# Sheet1.net
KiCad netlist of a schematic drawn in Altium Designer
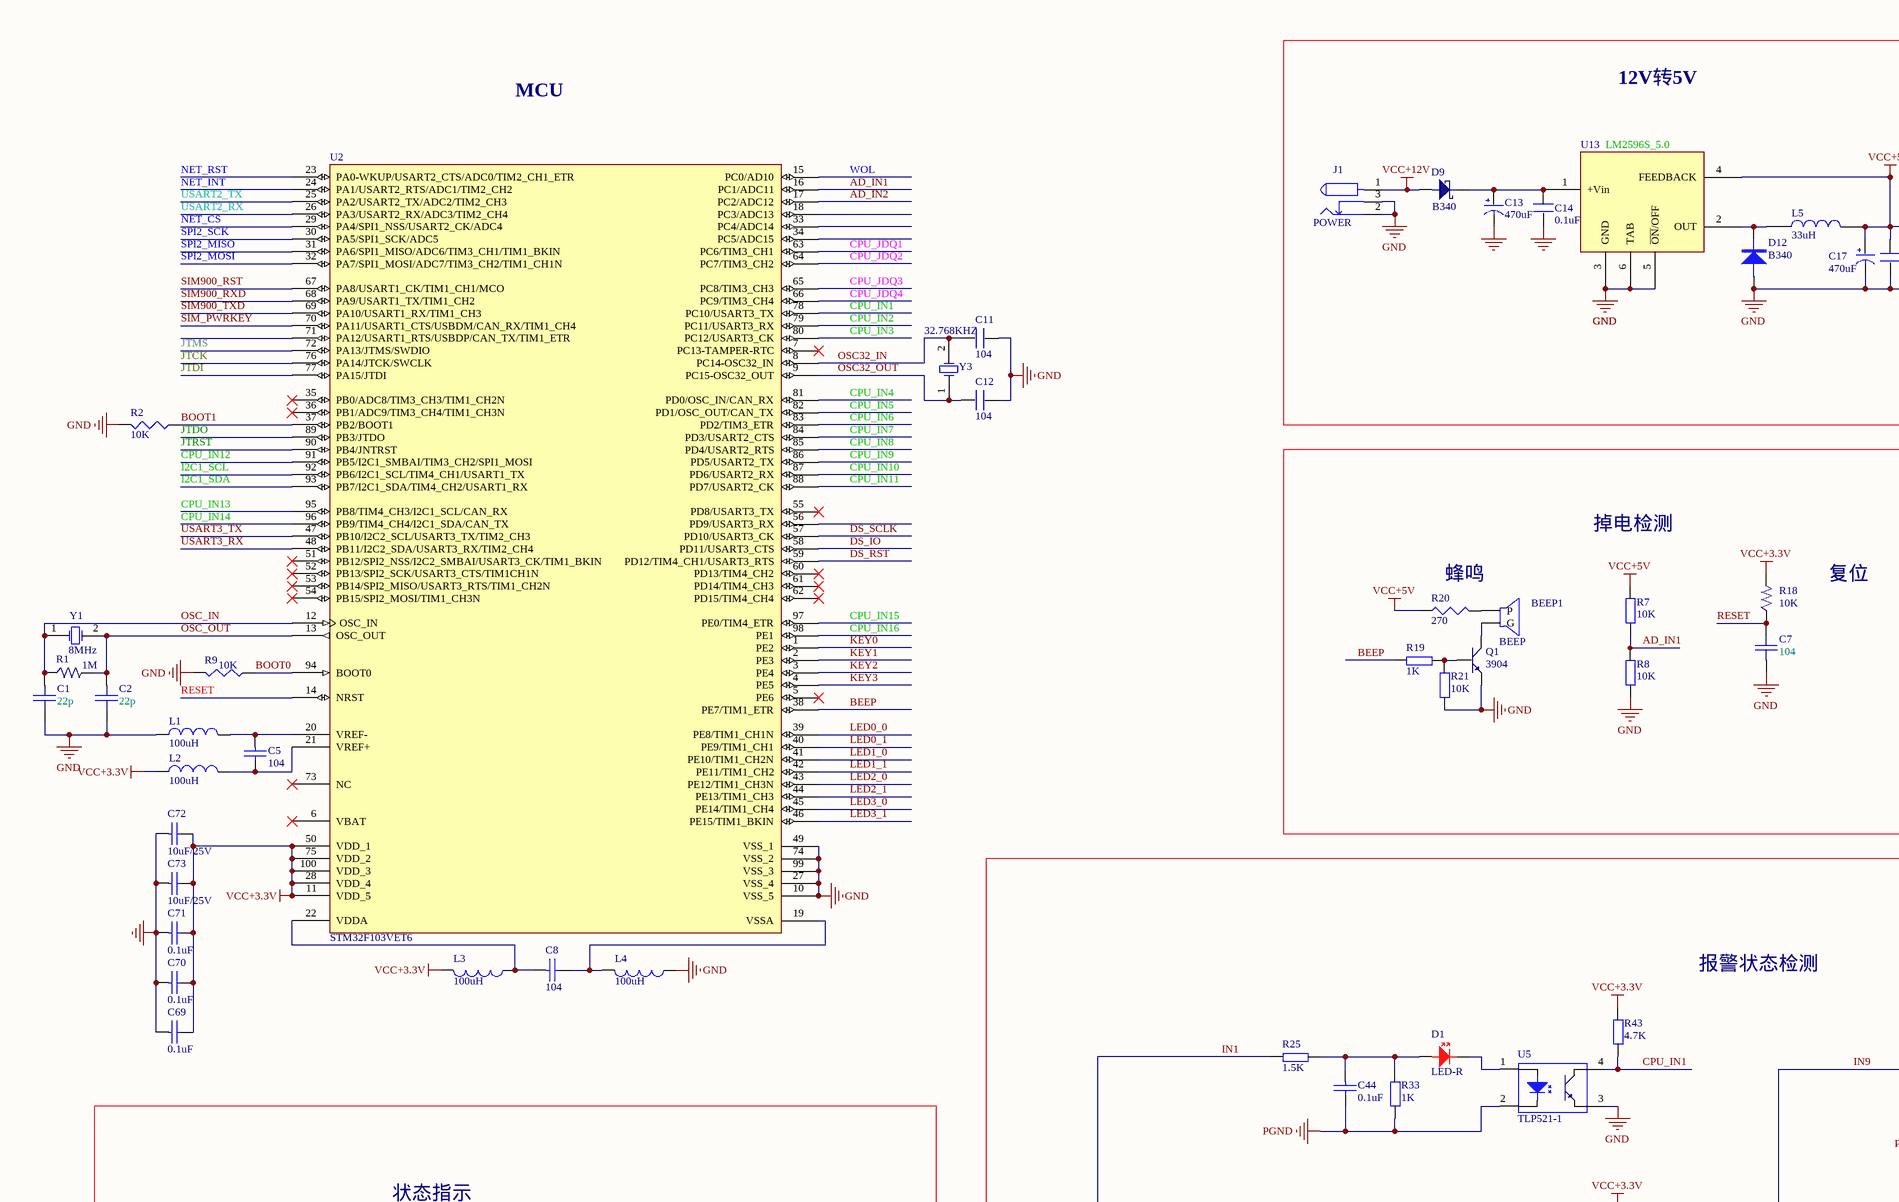
[diagram p0: Sheet1.SchDoc, top left]
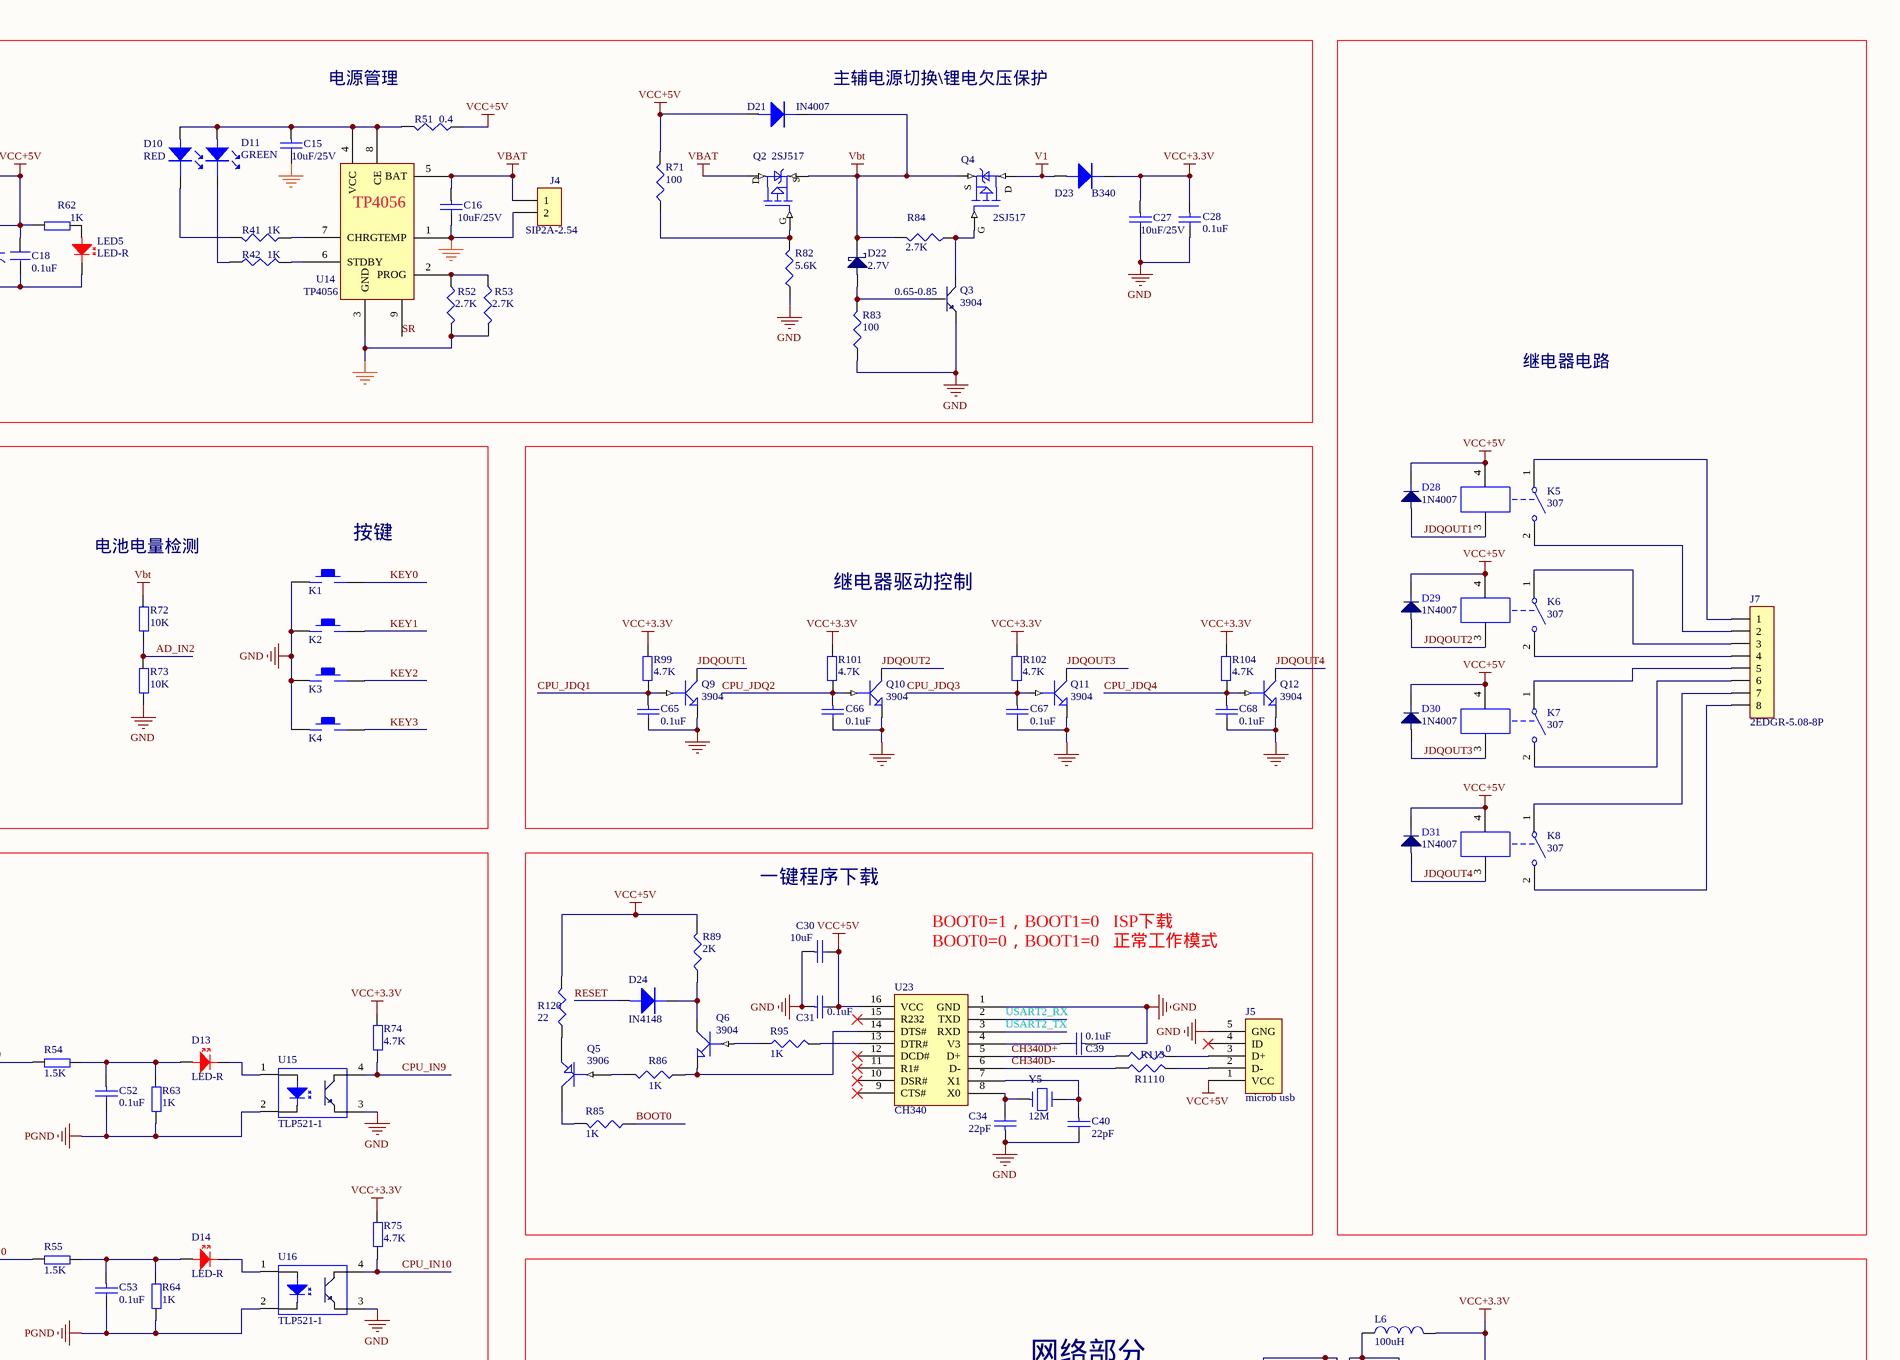
[diagram p1: Sheet1.SchDoc, top right]
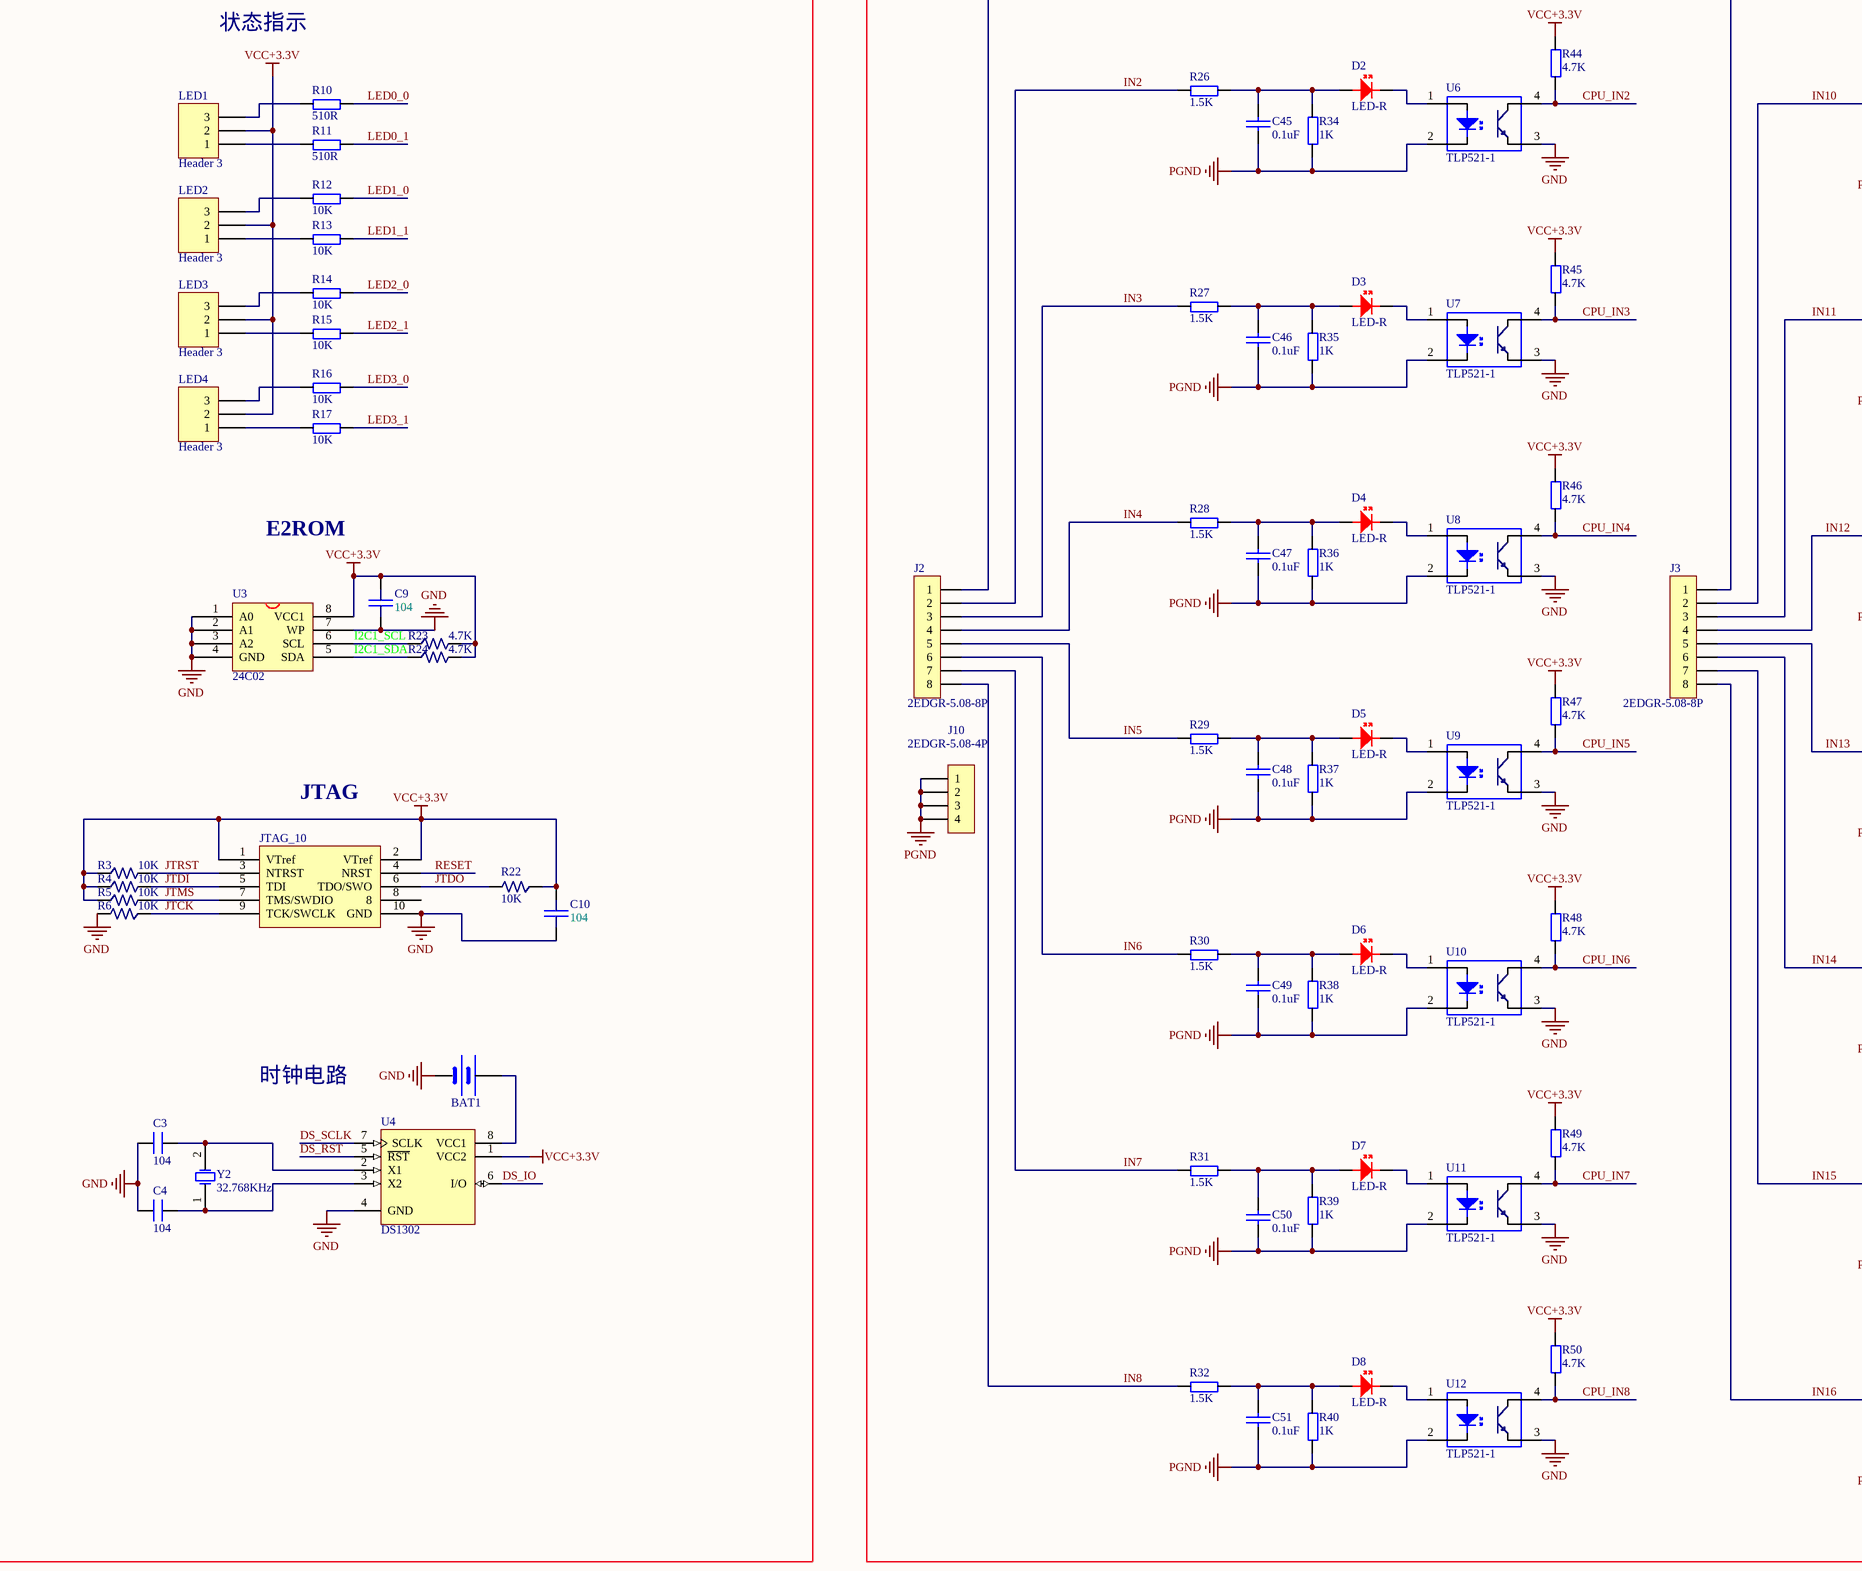
[diagram p2: Sheet1.SchDoc, bottom left]
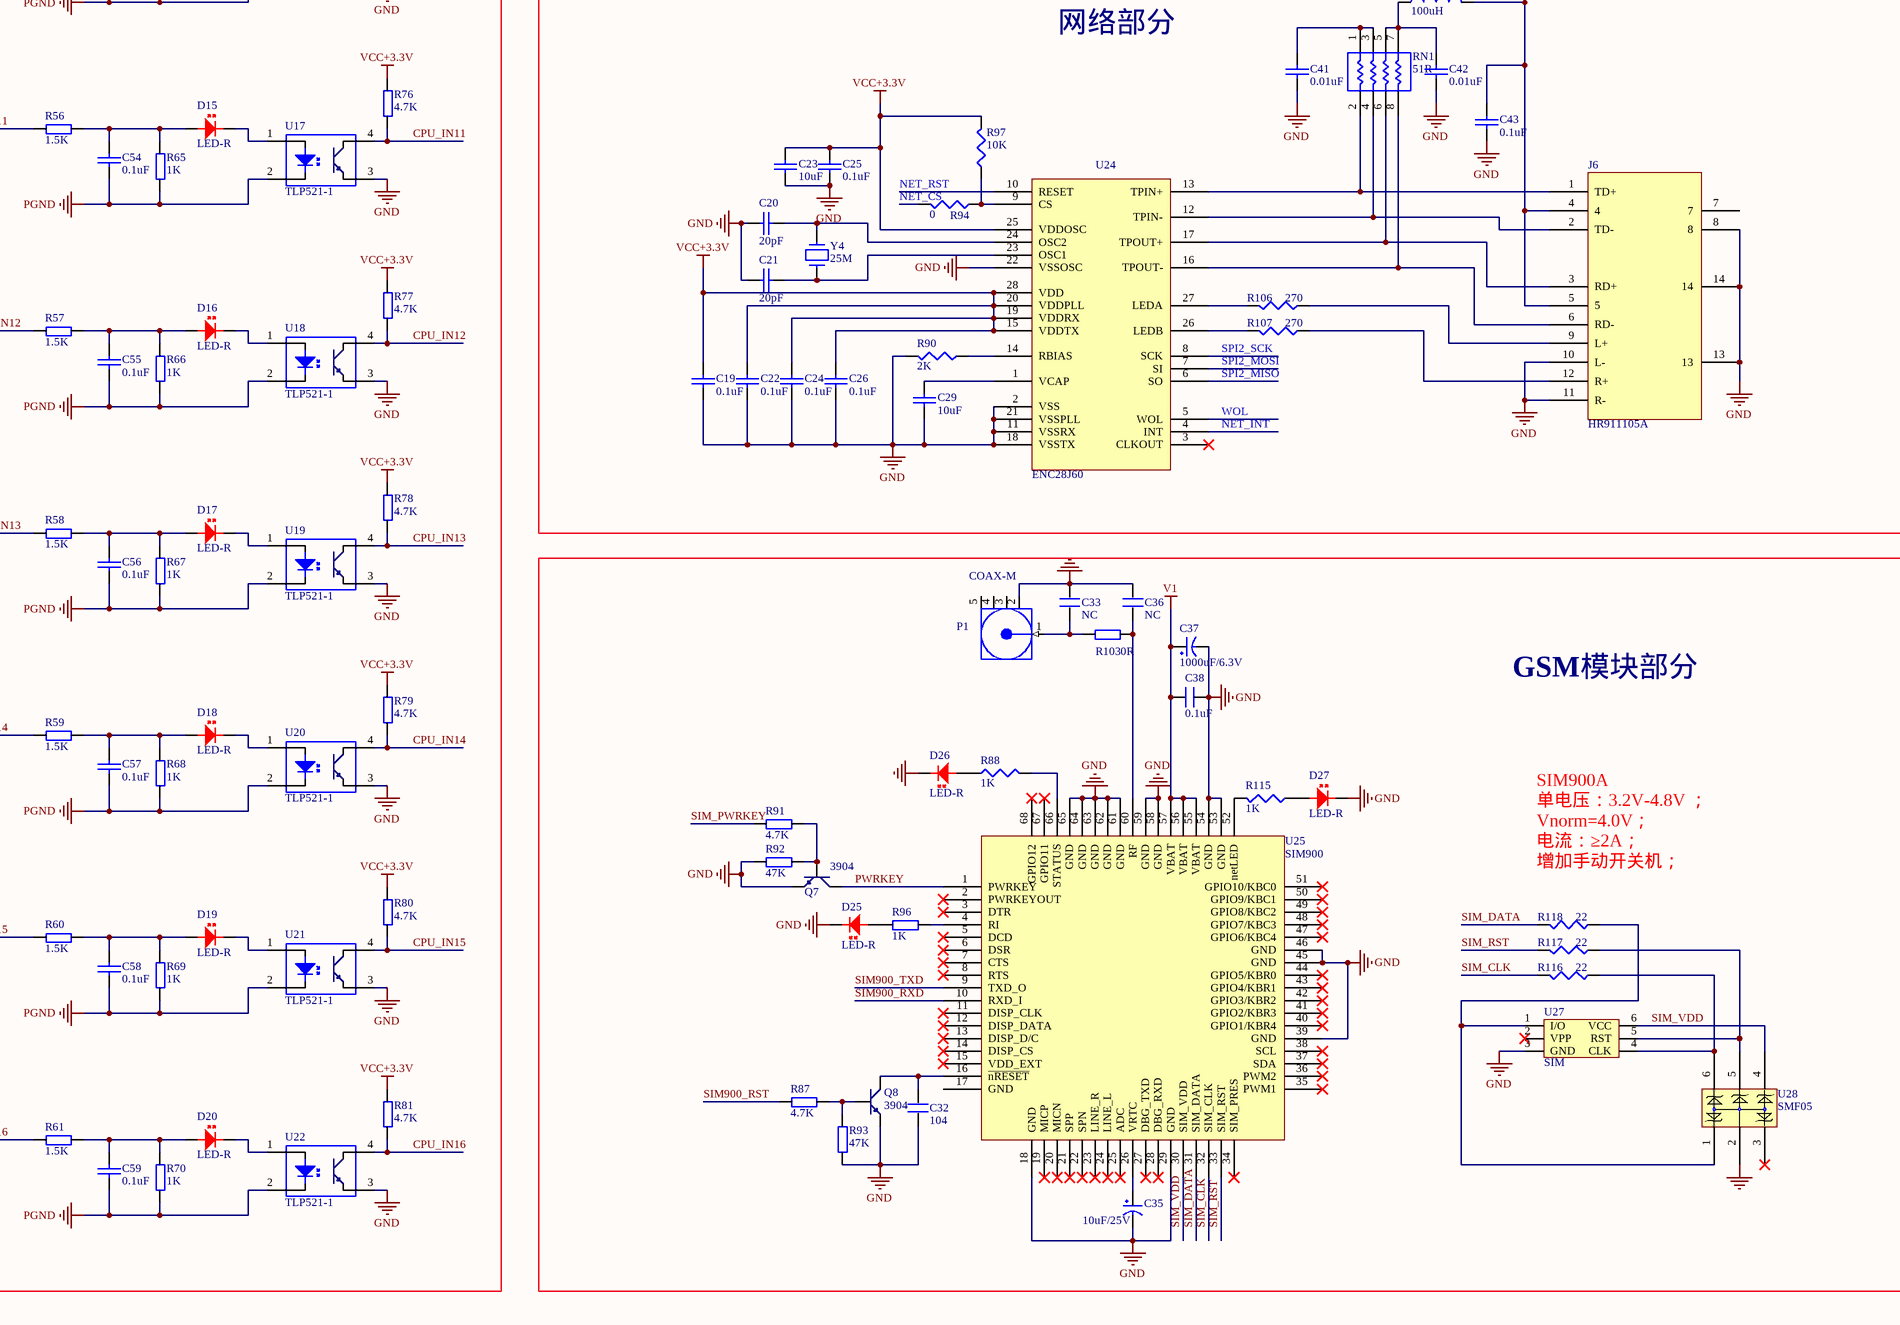
[diagram p3: Sheet1.SchDoc, bottom right]

(export (version "E")
  (design (tool "Eeschema 10.0.6"))
  (components
    (comp (ref "BAT1") (value "BATT") (footprint "CR2032") (libsource (lib "mylib") (part "BAT")))
    (comp (ref "BEEP1") (value "BEEP") (footprint "BEEP-12") (libsource (lib "mylib") (part "BEEP")))
    (comp (ref "C1")
      (value "22p")
      (footprint "0805")
      (description "陶瓷电容")
      (libsource (lib "8CF_V6") (part "CAP"))
    )
    (comp (ref "C2")
      (value "22p")
      (footprint "0805")
      (description "陶瓷电容")
      (libsource (lib "8CF_V6") (part "CAP"))
    )
    (comp (ref "C3") (value "104") (footprint "0805") (libsource (lib "mylib") (part "C")))
    (comp (ref "C4") (value "104") (footprint "0805") (libsource (lib "mylib") (part "C")))
    (comp (ref "C5") (value "104") (footprint "0805") (libsource (lib "INSPUR_SCH") (part "CAP")))
    (comp (ref "C7")
      (value "104")
      (footprint "0805")
      (description "陶瓷电容")
      (libsource (lib "8CF_V6") (part "CAP"))
    )
    (comp (ref "C8") (value "104") (footprint "0805") (libsource (lib "INSPUR_SCH") (part "CAP")))
    (comp (ref "C9")
      (value "104")
      (footprint "0805")
      (description "陶瓷电容")
      (libsource (lib "8CF_V6") (part "CAP"))
    )
    (comp (ref "C10")
      (value "104")
      (footprint "0805")
      (description "陶瓷电容")
      (libsource (lib "8CF_V6") (part "CAP"))
    )
    (comp (ref "C11") (value "104") (footprint "0805") (libsource (lib "mylib") (part "C")))
    (comp (ref "C12") (value "104") (footprint "0805") (libsource (lib "mylib") (part "C")))
    (comp (ref "C13") (value "470uF") (footprint "RB3.5") (libsource (lib "战舰STM32开发板底板") (part "CAP")))
    (comp (ref "C14") (value "0.1uF") (footprint "0805") (libsource (lib "mylib") (part "C")))
    (comp (ref "C15") (value "10uF/25V") (footprint "0805") (libsource (lib "*") (part "CAP")))
    (comp (ref "C16") (value "10uF/25V") (footprint "0805") (libsource (lib "*") (part "CAP")))
    (comp (ref "C17") (value "470uF") (footprint "RB3.5") (libsource (lib "战舰STM32开发板底板") (part "CAP")))
    (comp (ref "C18") (value "0.1uF") (footprint "0805") (libsource (lib "mylib") (part "C")))
    (comp (ref "C19") (value "0.1uF") (footprint "0805") (libsource (lib "INSPUR_SCH") (part "CAP")))
    (comp (ref "C20") (value "20pF") (footprint "0805") (libsource (lib "INSPUR_SCH") (part "CAP")))
    (comp (ref "C21") (value "20pF") (footprint "0805") (libsource (lib "INSPUR_SCH") (part "CAP")))
    (comp (ref "C22") (value "0.1uF") (footprint "0805") (libsource (lib "INSPUR_SCH") (part "CAP")))
    (comp (ref "C23")
      (value "10uF")
      (footprint "0805")
      (description "0.1uF")
      (libsource (lib "INSPUR_SCH") (part "CAP"))
    )
    (comp (ref "C24") (value "0.1uF") (footprint "0805") (libsource (lib "INSPUR_SCH") (part "CAP")))
    (comp (ref "C25") (value "0.1uF") (footprint "0805") (libsource (lib "INSPUR_SCH") (part "CAP")))
    (comp (ref "C26") (value "0.1uF") (footprint "0805") (libsource (lib "INSPUR_SCH") (part "CAP")))
    (comp (ref "C27") (value "10uF/25V") (footprint "0805") (libsource (lib "*") (part "CAP")))
    (comp (ref "C28") (value "0.1uF") (footprint "0805") (libsource (lib "INSPUR_SCH") (part "CAP")))
    (comp (ref "C29") (value "10uF") (footprint "0805") (libsource (lib "INSPUR_SCH") (part "CAP")))
    (comp (ref "C30")
      (value "10uF")
      (footprint "0805")
      (description "0.1uF")
      (libsource (lib "INSPUR_SCH") (part "CAP"))
    )
    (comp (ref "C31") (value "0.1uF") (footprint "0805") (libsource (lib "INSPUR_SCH") (part "CAP")))
    (comp (ref "C32") (value "104") (footprint "0805") (libsource (lib "mylib") (part "C")))
    (comp (ref "C33") (value "NC") (footprint "0805") (libsource (lib "mylib") (part "C")))
    (comp (ref "C34")
      (value "22pF")
      (footprint "0805")
      (description "0.1uF")
      (libsource (lib "INSPUR_SCH") (part "CAP"))
    )
    (comp (ref "C35") (value "10uF/25V") (footprint "1206") (libsource (lib "mylib") (part "CAP")))
    (comp (ref "C36") (value "NC") (footprint "0805") (libsource (lib "mylib") (part "C")))
    (comp (ref "C37") (value "1000uF/6.3V") (footprint "7343") (libsource (lib "") (part "CAP_1")))
    (comp (ref "C38") (value "0.1uF") (footprint "0805") (libsource (lib "mylib") (part "C")))
    (comp (ref "C39") (value "0.1uF") (footprint "0805") (libsource (lib "INSPUR_SCH") (part "CAP")))
    (comp (ref "C40")
      (value "22pF")
      (footprint "0805")
      (description "0.1uF")
      (libsource (lib "INSPUR_SCH") (part "CAP"))
    )
    (comp (ref "C41") (value "0.01uF") (footprint "0805") (libsource (lib "INSPUR_SCH") (part "CAP")))
    (comp (ref "C42") (value "0.01uF") (footprint "0805") (libsource (lib "INSPUR_SCH") (part "CAP")))
    (comp (ref "C43") (value "0.1uF") (footprint "0805") (libsource (lib "INSPUR_SCH") (part "CAP")))
    (comp (ref "C44") (value "0.1uF") (footprint "0805") (libsource (lib "INSPUR_SCH") (part "CAP")))
    (comp (ref "C45") (value "0.1uF") (footprint "0805") (libsource (lib "INSPUR_SCH") (part "CAP")))
    (comp (ref "C46") (value "0.1uF") (footprint "0805") (libsource (lib "INSPUR_SCH") (part "CAP")))
    (comp (ref "C47") (value "0.1uF") (footprint "0805") (libsource (lib "INSPUR_SCH") (part "CAP")))
    (comp (ref "C48") (value "0.1uF") (footprint "0805") (libsource (lib "INSPUR_SCH") (part "CAP")))
    (comp (ref "C49") (value "0.1uF") (footprint "0805") (libsource (lib "INSPUR_SCH") (part "CAP")))
    (comp (ref "C50") (value "0.1uF") (footprint "0805") (libsource (lib "INSPUR_SCH") (part "CAP")))
    (comp (ref "C51") (value "0.1uF") (footprint "0805") (libsource (lib "INSPUR_SCH") (part "CAP")))
    (comp (ref "C52") (value "0.1uF") (footprint "0805") (libsource (lib "INSPUR_SCH") (part "CAP")))
    (comp (ref "C53") (value "0.1uF") (footprint "0805") (libsource (lib "INSPUR_SCH") (part "CAP")))
    (comp (ref "C54") (value "0.1uF") (footprint "0805") (libsource (lib "INSPUR_SCH") (part "CAP")))
    (comp (ref "C55") (value "0.1uF") (footprint "0805") (libsource (lib "INSPUR_SCH") (part "CAP")))
    (comp (ref "C56") (value "0.1uF") (footprint "0805") (libsource (lib "INSPUR_SCH") (part "CAP")))
    (comp (ref "C57") (value "0.1uF") (footprint "0805") (libsource (lib "INSPUR_SCH") (part "CAP")))
    (comp (ref "C58") (value "0.1uF") (footprint "0805") (libsource (lib "INSPUR_SCH") (part "CAP")))
    (comp (ref "C59") (value "0.1uF") (footprint "0805") (libsource (lib "INSPUR_SCH") (part "CAP")))
    (comp (ref "C65") (value "0.1uF") (footprint "0805") (libsource (lib "INSPUR_SCH") (part "CAP")))
    (comp (ref "C66") (value "0.1uF") (footprint "0805") (libsource (lib "INSPUR_SCH") (part "CAP")))
    (comp (ref "C67") (value "0.1uF") (footprint "0805") (libsource (lib "INSPUR_SCH") (part "CAP")))
    (comp (ref "C68") (value "0.1uF") (footprint "0805") (libsource (lib "INSPUR_SCH") (part "CAP")))
    (comp (ref "C69") (value "0.1uF") (footprint "0805") (libsource (lib "INSPUR_SCH") (part "CAP")))
    (comp (ref "C70") (value "0.1uF") (footprint "0805") (libsource (lib "INSPUR_SCH") (part "CAP")))
    (comp (ref "C71") (value "0.1uF") (footprint "0805") (libsource (lib "*") (part "CAP")))
    (comp (ref "C72") (value "10uF/25V") (footprint "0805") (libsource (lib "*") (part "CAP")))
    (comp (ref "C73") (value "10uF/25V") (footprint "0805") (libsource (lib "*") (part "CAP")))
    (comp (ref "D1")
      (value "LED-R")
      (footprint "0805-LED")
      (description "红色LED")
      (libsource (lib "mylib") (part "LED-RED"))
    )
    (comp (ref "D2")
      (value "LED-R")
      (footprint "0805-LED")
      (description "红色LED")
      (libsource (lib "mylib") (part "LED-RED"))
    )
    (comp (ref "D3")
      (value "LED-R")
      (footprint "0805-LED")
      (description "红色LED")
      (libsource (lib "mylib") (part "LED-RED"))
    )
    (comp (ref "D4")
      (value "LED-R")
      (footprint "0805-LED")
      (description "红色LED")
      (libsource (lib "mylib") (part "LED-RED"))
    )
    (comp (ref "D5")
      (value "LED-R")
      (footprint "0805-LED")
      (description "红色LED")
      (libsource (lib "mylib") (part "LED-RED"))
    )
    (comp (ref "D6")
      (value "LED-R")
      (footprint "0805-LED")
      (description "红色LED")
      (libsource (lib "mylib") (part "LED-RED"))
    )
    (comp (ref "D7")
      (value "LED-R")
      (footprint "0805-LED")
      (description "红色LED")
      (libsource (lib "mylib") (part "LED-RED"))
    )
    (comp (ref "D8")
      (value "LED-R")
      (footprint "0805-LED")
      (description "红色LED")
      (libsource (lib "mylib") (part "LED-RED"))
    )
    (comp (ref "D9")
      (value "B340")
      (footprint "SMB")
      (description "肖特基二极管")
      (libsource (lib "mylib") (part "1N5824(SS54)"))
    )
    (comp (ref "D10") (value "RED") (footprint "LED-0805") (libsource (lib "*") (part "LED")))
    (comp (ref "D11") (value "GREEN") (footprint "LED-0805") (libsource (lib "*") (part "LED")))
    (comp (ref "D12") (value "B340") (footprint "SMB") (libsource (lib "INSPUR_SCH") (part "DIODE")))
    (comp (ref "D13")
      (value "LED-R")
      (footprint "0805-LED")
      (description "红色LED")
      (libsource (lib "mylib") (part "LED-RED"))
    )
    (comp (ref "D14")
      (value "LED-R")
      (footprint "0805-LED")
      (description "红色LED")
      (libsource (lib "mylib") (part "LED-RED"))
    )
    (comp (ref "D15")
      (value "LED-R")
      (footprint "0805-LED")
      (description "红色LED")
      (libsource (lib "mylib") (part "LED-RED"))
    )
    (comp (ref "D16")
      (value "LED-R")
      (footprint "0805-LED")
      (description "红色LED")
      (libsource (lib "mylib") (part "LED-RED"))
    )
    (comp (ref "D17")
      (value "LED-R")
      (footprint "0805-LED")
      (description "红色LED")
      (libsource (lib "mylib") (part "LED-RED"))
    )
    (comp (ref "D18")
      (value "LED-R")
      (footprint "0805-LED")
      (description "红色LED")
      (libsource (lib "mylib") (part "LED-RED"))
    )
    (comp (ref "D19")
      (value "LED-R")
      (footprint "0805-LED")
      (description "红色LED")
      (libsource (lib "mylib") (part "LED-RED"))
    )
    (comp (ref "D20")
      (value "LED-R")
      (footprint "0805-LED")
      (description "红色LED")
      (libsource (lib "mylib") (part "LED-RED"))
    )
    (comp (ref "D21")
      (value "IN4007")
      (footprint "SMA(DO-214AC)")
      (libsource (lib "INSPUR_SCH") (part "DIODE"))
    )
    (comp (ref "D22")
      (value "2.7V")
      (footprint "sod-123")
      (description "3V稳压管")
      (libsource (lib "mylib") (part "1N5824(SS54)"))
    )
    (comp (ref "D23") (value "B340") (footprint "SMB") (libsource (lib "INSPUR_SCH") (part "DIODE")))
    (comp (ref "D24") (value "IN4148") (footprint "SOD-23") (libsource (lib "INSPUR_SCH") (part "DIODE")))
    (comp (ref "D25")
      (value "LED-R")
      (footprint "LED-DIP")
      (description "红色LED")
      (libsource (lib "mylib") (part "LED-RED"))
    )
    (comp (ref "D26")
      (value "LED-R")
      (footprint "LED-DIP")
      (description "红色LED")
      (libsource (lib "mylib") (part "LED-RED"))
    )
    (comp (ref "D27")
      (value "LED-R")
      (footprint "LED-DIP")
      (description "红色LED")
      (libsource (lib "mylib") (part "LED-RED"))
    )
    (comp (ref "D28")
      (value "1N4007")
      (footprint "DO-214AC(SMA)")
      (description "1A整流二极管")
      (libsource (lib "mylib") (part "1N4007"))
    )
    (comp (ref "D29")
      (value "1N4007")
      (footprint "DO-214AC(SMA)")
      (description "1A整流二极管")
      (libsource (lib "mylib") (part "1N4007"))
    )
    (comp (ref "D30")
      (value "1N4007")
      (footprint "DO-214AC(SMA)")
      (description "1A整流二极管")
      (libsource (lib "mylib") (part "1N4007"))
    )
    (comp (ref "D31")
      (value "1N4007")
      (footprint "DO-214AC(SMA)")
      (description "1A整流二极管")
      (libsource (lib "mylib") (part "1N4007"))
    )
    (comp (ref "J1") (value "POWER") (footprint "DC10B") (libsource (lib "战舰STM32开发板底板") (part "POW")))
    (comp (ref "J2")
      (value "2EDGR-5.08-8P")
      (footprint "2EDGR-5.08-8P")
      (description "端子")
      (libsource (lib "mylib") (part "2EDGR-5.08-8P"))
    )
    (comp (ref "J3")
      (value "2EDGR-5.08-8P")
      (footprint "2EDGR-5.08-8P")
      (description "端子")
      (libsource (lib "mylib") (part "2EDGR-5.08-8P"))
    )
    (comp (ref "J4") (value "SIP2A-2.54") (footprint "2.54") (libsource (lib "*") (part "SIP2A-2.50（带槽）")))
    (comp (ref "J5")
      (value "microb usb")
      (footprint "USB_micro")
      (libsource (lib "INSPUR_SCH") (part "microb usb"))
    )
    (comp (ref "J6")
      (value "HR911105A")
      (footprint "HR911105A")
      (libsource (lib "INSPUR_SCH") (part "HR911105A"))
    )
    (comp (ref "J7")
      (value "2EDGR-5.08-8P")
      (footprint "2EDGR-5.08-8P")
      (description "端子")
      (libsource (lib "") (part "2EDGR-5.08-8P_1"))
    )
    (comp (ref "J10")
      (value "2EDGR-5.08-4P")
      (footprint "2EDGR-5.08-4P")
      (libsource (lib "INSPUR_SCH") (part "SIP4A-2.50(带槽)"))
    )
    (comp (ref "JTAG_1") (value "JTAG_10") (footprint "JTAG_10") (libsource (lib "mylib") (part "JTAG_10")))
    (comp (ref "K1") (value "KEY_M") (footprint "KEY_M") (libsource (lib "mylib") (part "KEY_M")))
    (comp (ref "K2") (value "KEY_M") (footprint "KEY_M") (libsource (lib "mylib") (part "KEY_M")))
    (comp (ref "K3") (value "KEY_M") (footprint "KEY_M") (libsource (lib "mylib") (part "KEY_M")))
    (comp (ref "K4") (value "KEY_M") (footprint "KEY_M") (libsource (lib "mylib") (part "KEY_M")))
    (comp (ref "K5")
      (value "307")
      (footprint "RELAY-SONGCHUAN")
      (description "继电器")
      (libsource (lib "mylib") (part "JDQ_307"))
    )
    (comp (ref "K6")
      (value "307")
      (footprint "RELAY-SONGCHUAN")
      (description "继电器")
      (libsource (lib "mylib") (part "JDQ_307"))
    )
    (comp (ref "K7")
      (value "307")
      (footprint "RELAY-SONGCHUAN")
      (description "继电器")
      (libsource (lib "mylib") (part "JDQ_307"))
    )
    (comp (ref "K8")
      (value "307")
      (footprint "RELAY-SONGCHUAN")
      (description "继电器")
      (libsource (lib "mylib") (part "JDQ_307"))
    )
    (comp (ref "L1") (value "100uH") (footprint "0805") (libsource (lib "INSPUR_SCH") (part "INDUCTOR")))
    (comp (ref "L2") (value "100uH") (footprint "0805") (libsource (lib "INSPUR_SCH") (part "INDUCTOR")))
    (comp (ref "L3") (value "100uH") (footprint "0805") (libsource (lib "INSPUR_SCH") (part "INDUCTOR")))
    (comp (ref "L4") (value "100uH") (footprint "0805") (libsource (lib "INSPUR_SCH") (part "INDUCTOR")))
    (comp (ref "L5") (value "33uH") (footprint "INDUCTOR-1212") (libsource (lib "mylib") (part "INDUCTOR")))
    (comp (ref "L6") (value "100uH") (footprint "0805") (libsource (lib "INSPUR_SCH") (part "INDUCTOR")))
    (comp (ref "LED1")
      (value "Header 3")
      (footprint "HDR1X3")
      (description "Header, 3-Pin")
      (fields (field (name "PUBLISHER") "Altium Limited"))
      (libsource (lib "Miscellaneous Connectors") (part "Header 3"))
    )
    (comp (ref "LED2")
      (value "Header 3")
      (footprint "HDR1X3")
      (description "Header, 3-Pin")
      (fields (field (name "PUBLISHER") "Altium Limited"))
      (libsource (lib "Miscellaneous Connectors") (part "Header 3"))
    )
    (comp (ref "LED3")
      (value "Header 3")
      (footprint "HDR1X3")
      (description "Header, 3-Pin")
      (fields (field (name "PUBLISHER") "Altium Limited"))
      (libsource (lib "Miscellaneous Connectors") (part "Header 3"))
    )
    (comp (ref "LED4")
      (value "Header 3")
      (footprint "HDR1X3")
      (description "Header, 3-Pin")
      (fields (field (name "PUBLISHER") "Altium Limited"))
      (libsource (lib "Miscellaneous Connectors") (part "Header 3"))
    )
    (comp (ref "LED5")
      (value "LED-R")
      (footprint "LED-0805")
      (description "红色LED")
      (libsource (lib "mylib") (part "LED-RED"))
    )
    (comp (ref "P1")
      (value "COAX-M")
      (footprint "ST-TH1")
      (description "SMA-J-P-H-ST-TH1")
      (fields (field (name "PUBLISHER") "Altium Limited"))
      (libsource (lib "Miscellaneous Connectors") (part "COAX-M"))
    )
    (comp (ref "Q1")
      (value "3904")
      (footprint "SOT-23")
      (description "8050/BCW846/BCW847")
      (libsource (lib "mylib") (part "NPN"))
    )
    (comp (ref "Q2") (value "2SJ517") (footprint "SOT-89") (libsource (lib "*") (part "MOSFET P_1")))
    (comp (ref "Q3")
      (value "3904")
      (footprint "SOT-23")
      (description "8050/BCW846/BCW847")
      (libsource (lib "mylib") (part "NPN"))
    )
    (comp (ref "Q4") (value "2SJ517") (footprint "SOT-89") (libsource (lib "*") (part "MOSFET P_1")))
    (comp (ref "Q5") (value "3906") (footprint "SOT-23") (libsource (lib "INSPUR_SCH") (part "PNP1")))
    (comp (ref "Q6") (value "3904") (footprint "SOT-23") (libsource (lib "INSPUR_SCH") (part "NPN1")))
    (comp (ref "Q7")
      (value "3904")
      (footprint "SOT-23R")
      (description "8050/BCW846/BCW847")
      (libsource (lib "mylib") (part "NPN"))
    )
    (comp (ref "Q8")
      (value "3904")
      (footprint "SOT-23R")
      (description "8050/BCW846/BCW847")
      (libsource (lib "mylib") (part "NPN"))
    )
    (comp (ref "Q9") (value "3904") (footprint "SOT-23") (libsource (lib "INSPUR_SCH") (part "NPN1")))
    (comp (ref "Q10") (value "3904") (footprint "SOT-23") (libsource (lib "INSPUR_SCH") (part "NPN1")))
    (comp (ref "Q11") (value "3904") (footprint "SOT-23") (libsource (lib "INSPUR_SCH") (part "NPN1")))
    (comp (ref "Q12") (value "3904") (footprint "SOT-23") (libsource (lib "INSPUR_SCH") (part "NPN1")))
    (comp (ref "R1")
      (value "1M")
      (footprint "0805")
      (description "高精度电阻")
      (libsource (lib "8CF_V6") (part "RES-1%"))
    )
    (comp (ref "R2") (value "10K") (footprint "0805") (libsource (lib "INSPUR_SCH") (part "RES1")))
    (comp (ref "R3")
      (value "10K")
      (footprint "0805")
      (description "高精度电阻")
      (libsource (lib "8CF_V6") (part "RES-1%"))
    )
    (comp (ref "R4")
      (value "10K")
      (footprint "0805")
      (description "高精度电阻")
      (libsource (lib "8CF_V6") (part "RES-1%"))
    )
    (comp (ref "R5")
      (value "10K")
      (footprint "0805")
      (description "高精度电阻")
      (libsource (lib "8CF_V6") (part "RES-1%"))
    )
    (comp (ref "R6")
      (value "10K")
      (footprint "0805")
      (description "高精度电阻")
      (libsource (lib "8CF_V6") (part "RES-1%"))
    )
    (comp (ref "R7") (value "10K") (footprint "0805") (libsource (lib "mylib") (part "Res")))
    (comp (ref "R8") (value "10K") (footprint "0805") (libsource (lib "mylib") (part "Res")))
    (comp (ref "R9") (value "10K") (footprint "0805") (libsource (lib "INSPUR_SCH") (part "RES1")))
    (comp (ref "R10") (value "510R") (footprint "0805") (libsource (lib "mylib") (part "Res")))
    (comp (ref "R11") (value "510R") (footprint "0805") (libsource (lib "mylib") (part "Res")))
    (comp (ref "R12") (value "10K") (footprint "0805") (libsource (lib "mylib") (part "Res")))
    (comp (ref "R13") (value "10K") (footprint "0805") (libsource (lib "mylib") (part "Res")))
    (comp (ref "R14") (value "10K") (footprint "0805") (libsource (lib "mylib") (part "Res")))
    (comp (ref "R15") (value "10K") (footprint "0805") (libsource (lib "mylib") (part "Res")))
    (comp (ref "R16") (value "10K") (footprint "0805") (libsource (lib "mylib") (part "Res")))
    (comp (ref "R17") (value "10K") (footprint "0805") (libsource (lib "mylib") (part "Res")))
    (comp (ref "R18")
      (value "10K")
      (footprint "0805")
      (description "高精度电阻")
      (libsource (lib "8CF_V6") (part "RES-1%"))
    )
    (comp (ref "R19") (value "1K") (footprint "0805") (libsource (lib "mylib") (part "R")))
    (comp (ref "R20") (value "270") (footprint "0805") (libsource (lib "INSPUR_SCH") (part "RES1")))
    (comp (ref "R21") (value "10K") (footprint "0805") (libsource (lib "mylib") (part "R")))
    (comp (ref "R22")
      (value "10K")
      (footprint "0805")
      (description "高精度电阻")
      (libsource (lib "8CF_V6") (part "RES-1%"))
    )
    (comp (ref "R23")
      (value "4.7K")
      (footprint "0805")
      (description "高精度电阻")
      (libsource (lib "8CF_V6") (part "RES-1%"))
    )
    (comp (ref "R24")
      (value "4.7K")
      (footprint "0805")
      (description "高精度电阻")
      (libsource (lib "8CF_V6") (part "RES-1%"))
    )
    (comp (ref "R25") (value "1.5K") (footprint "0805") (libsource (lib "mylib") (part "Res")))
    (comp (ref "R26") (value "1.5K") (footprint "0805") (libsource (lib "mylib") (part "Res")))
    (comp (ref "R27") (value "1.5K") (footprint "0805") (libsource (lib "mylib") (part "Res")))
    (comp (ref "R28") (value "1.5K") (footprint "0805") (libsource (lib "mylib") (part "Res")))
    (comp (ref "R29") (value "1.5K") (footprint "0805") (libsource (lib "mylib") (part "Res")))
    (comp (ref "R30") (value "1.5K") (footprint "0805") (libsource (lib "mylib") (part "Res")))
    (comp (ref "R31") (value "1.5K") (footprint "0805") (libsource (lib "mylib") (part "Res")))
    (comp (ref "R32") (value "1.5K") (footprint "0805") (libsource (lib "mylib") (part "Res")))
    (comp (ref "R33") (value "1K") (footprint "0805") (libsource (lib "mylib") (part "Res")))
    (comp (ref "R34") (value "1K") (footprint "0805") (libsource (lib "mylib") (part "Res")))
    (comp (ref "R35") (value "1K") (footprint "0805") (libsource (lib "mylib") (part "Res")))
    (comp (ref "R36") (value "1K") (footprint "0805") (libsource (lib "mylib") (part "Res")))
    (comp (ref "R37") (value "1K") (footprint "0805") (libsource (lib "mylib") (part "Res")))
    (comp (ref "R38") (value "1K") (footprint "0805") (libsource (lib "mylib") (part "Res")))
    (comp (ref "R39") (value "1K") (footprint "0805") (libsource (lib "mylib") (part "Res")))
    (comp (ref "R40") (value "1K") (footprint "0805") (libsource (lib "mylib") (part "Res")))
    (comp (ref "R41") (value "1K") (footprint "0805") (libsource (lib "*") (part "RES1")))
    (comp (ref "R42") (value "1K") (footprint "0805") (libsource (lib "*") (part "RES1")))
    (comp (ref "R43") (value "4.7K") (footprint "0805") (libsource (lib "mylib") (part "Res")))
    (comp (ref "R44") (value "4.7K") (footprint "0805") (libsource (lib "mylib") (part "Res")))
    (comp (ref "R45") (value "4.7K") (footprint "0805") (libsource (lib "mylib") (part "Res")))
    (comp (ref "R46") (value "4.7K") (footprint "0805") (libsource (lib "mylib") (part "Res")))
    (comp (ref "R47") (value "4.7K") (footprint "0805") (libsource (lib "mylib") (part "Res")))
    (comp (ref "R48") (value "4.7K") (footprint "0805") (libsource (lib "mylib") (part "Res")))
    (comp (ref "R49") (value "4.7K") (footprint "0805") (libsource (lib "mylib") (part "Res")))
    (comp (ref "R50") (value "4.7K") (footprint "0805") (libsource (lib "mylib") (part "Res")))
    (comp (ref "R51") (value "0.4") (footprint "1206") (libsource (lib "*") (part "RES1")))
    (comp (ref "R52") (value "2.7K") (footprint "0805") (libsource (lib "*") (part "RES1")))
    (comp (ref "R53") (value "2.7K") (footprint "0805") (libsource (lib "*") (part "RES1")))
    (comp (ref "R54") (value "1.5K") (footprint "0805") (libsource (lib "mylib") (part "Res")))
    (comp (ref "R55") (value "1.5K") (footprint "0805") (libsource (lib "mylib") (part "Res")))
    (comp (ref "R56") (value "1.5K") (footprint "0805") (libsource (lib "mylib") (part "Res")))
    (comp (ref "R57") (value "1.5K") (footprint "0805") (libsource (lib "mylib") (part "Res")))
    (comp (ref "R58") (value "1.5K") (footprint "0805") (libsource (lib "mylib") (part "Res")))
    (comp (ref "R59") (value "1.5K") (footprint "0805") (libsource (lib "mylib") (part "Res")))
    (comp (ref "R60") (value "1.5K") (footprint "0805") (libsource (lib "mylib") (part "Res")))
    (comp (ref "R61") (value "1.5K") (footprint "0805") (libsource (lib "mylib") (part "Res")))
    (comp (ref "R62") (value "1K") (footprint "0805") (libsource (lib "mylib") (part "Res")))
    (comp (ref "R63") (value "1K") (footprint "0805") (libsource (lib "mylib") (part "Res")))
    (comp (ref "R64") (value "1K") (footprint "0805") (libsource (lib "mylib") (part "Res")))
    (comp (ref "R65") (value "1K") (footprint "0805") (libsource (lib "mylib") (part "Res")))
    (comp (ref "R66") (value "1K") (footprint "0805") (libsource (lib "mylib") (part "Res")))
    (comp (ref "R67") (value "1K") (footprint "0805") (libsource (lib "mylib") (part "Res")))
    (comp (ref "R68") (value "1K") (footprint "0805") (libsource (lib "mylib") (part "Res")))
    (comp (ref "R69") (value "1K") (footprint "0805") (libsource (lib "mylib") (part "Res")))
    (comp (ref "R70") (value "1K") (footprint "0805") (libsource (lib "mylib") (part "Res")))
    (comp (ref "R71")
      (value "100")
      (footprint "0805")
      (description "Resistor")
      (libsource (lib "*") (part "RESISTOR"))
    )
    (comp (ref "R72") (value "10K") (footprint "0805") (libsource (lib "mylib") (part "Res")))
    (comp (ref "R73") (value "10K") (footprint "0805") (libsource (lib "mylib") (part "Res")))
    (comp (ref "R74") (value "4.7K") (footprint "0805") (libsource (lib "mylib") (part "Res")))
    (comp (ref "R75") (value "4.7K") (footprint "0805") (libsource (lib "mylib") (part "Res")))
    (comp (ref "R76") (value "4.7K") (footprint "0805") (libsource (lib "mylib") (part "Res")))
    (comp (ref "R77") (value "4.7K") (footprint "0805") (libsource (lib "mylib") (part "Res")))
    (comp (ref "R78") (value "4.7K") (footprint "0805") (libsource (lib "mylib") (part "Res")))
    (comp (ref "R79") (value "4.7K") (footprint "0805") (libsource (lib "mylib") (part "Res")))
    (comp (ref "R80") (value "4.7K") (footprint "0805") (libsource (lib "mylib") (part "Res")))
    (comp (ref "R81") (value "4.7K") (footprint "0805") (libsource (lib "mylib") (part "Res")))
    (comp (ref "R82")
      (value "5.6K")
      (footprint "0805")
      (description "Resistor")
      (libsource (lib "*") (part "RESISTOR"))
    )
    (comp (ref "R83")
      (value "100")
      (footprint "0805")
      (description "Resistor")
      (libsource (lib "*") (part "RESISTOR"))
    )
    (comp (ref "R84")
      (value "2.7K")
      (footprint "0805")
      (description "Resistor")
      (libsource (lib "*") (part "RESISTOR"))
    )
    (comp (ref "R85") (value "1K") (footprint "0805") (libsource (lib "INSPUR_SCH") (part "RES1")))
    (comp (ref "R86") (value "1K") (footprint "0805") (libsource (lib "INSPUR_SCH") (part "RES1")))
    (comp (ref "R87") (value "4.7K") (footprint "0805") (libsource (lib "mylib") (part "Res")))
    (comp (ref "R88") (value "1K") (footprint "0805") (libsource (lib "INSPUR_SCH") (part "RES1")))
    (comp (ref "R89") (value "2K") (footprint "0805") (libsource (lib "INSPUR_SCH") (part "RES1")))
    (comp (ref "R90") (value "2K") (footprint "0805") (libsource (lib "INSPUR_SCH") (part "RES1")))
    (comp (ref "R91") (value "4.7K") (footprint "0805") (libsource (lib "mylib") (part "Res")))
    (comp (ref "R92") (value "47K") (footprint "0805") (libsource (lib "mylib") (part "Res")))
    (comp (ref "R93") (value "47K") (footprint "0805") (libsource (lib "mylib") (part "Res")))
    (comp (ref "R94") (value "0") (footprint "0805") (libsource (lib "INSPUR_SCH") (part "RES1")))
    (comp (ref "R95") (value "1K") (footprint "0805") (libsource (lib "INSPUR_SCH") (part "RES1")))
    (comp (ref "R96") (value "1K") (footprint "0805") (libsource (lib "mylib") (part "Res")))
    (comp (ref "R97") (value "10K") (footprint "0805") (libsource (lib "INSPUR_SCH") (part "RES1")))
    (comp (ref "R99") (value "4.7K") (footprint "0805") (libsource (lib "mylib") (part "Res")))
    (comp (ref "R101") (value "4.7K") (footprint "0805") (libsource (lib "mylib") (part "Res")))
    (comp (ref "R102") (value "4.7K") (footprint "0805") (libsource (lib "mylib") (part "Res")))
    (comp (ref "R103") (value "0R") (footprint "0603") (libsource (lib "mylib") (part "Res")))
    (comp (ref "R104") (value "4.7K") (footprint "0805") (libsource (lib "mylib") (part "Res")))
    (comp (ref "R106") (value "270") (footprint "0805") (libsource (lib "INSPUR_SCH") (part "RES1")))
    (comp (ref "R107") (value "270") (footprint "0805") (libsource (lib "INSPUR_SCH") (part "RES1")))
    (comp (ref "R111") (value "0") (footprint "0805") (libsource (lib "INSPUR_SCH") (part "RES1")))
    (comp (ref "R113") (value "0") (footprint "0805") (libsource (lib "INSPUR_SCH") (part "RES1")))
    (comp (ref "R115") (value "1K") (footprint "0805") (libsource (lib "INSPUR_SCH") (part "RES1")))
    (comp (ref "R116") (value "22") (footprint "0805") (libsource (lib "INSPUR_SCH") (part "RES1")))
    (comp (ref "R117") (value "22") (footprint "0805") (libsource (lib "INSPUR_SCH") (part "RES1")))
    (comp (ref "R118") (value "22") (footprint "0805") (libsource (lib "INSPUR_SCH") (part "RES1")))
    (comp (ref "R120") (value "22") (footprint "0805") (libsource (lib "INSPUR_SCH") (part "RES1")))
    (comp (ref "RN1") (value "51R") (footprint "0603-4") (libsource (lib "INSPUR_SCH") (part "RESPACK")))
    (comp (ref "U2")
      (value "STM32F103VET6")
      (footprint "LQFP100_N")
      (description "STM32 ARM-based 32-bit MCU with 64 Kbytes Flash, 100-pin LQFP, Industrial Temperature")
      (fields (field (name "PUBLISHER") "Altium Limited"))
      (libsource (lib "mylib") (part "STM32F103VET6"))
    )
    (comp (ref "U3") (value "24C02") (footprint "SOP-8") (libsource (lib "战舰STM32开发板底板") (part "24C256")))
    (comp (ref "U4")
      (value "DS1302")
      (footprint "SOP-8")
      (description "实时时钟")
      (libsource (lib "mylib") (part "DS1302"))
    )
    (comp (ref "U5")
      (value "TLP521-1")
      (footprint "DIP4")
      (description "光耦")
      (libsource (lib "mylib") (part "TLP521"))
    )
    (comp (ref "U6")
      (value "TLP521-1")
      (footprint "DIP4")
      (description "光耦")
      (libsource (lib "mylib") (part "TLP521"))
    )
    (comp (ref "U7")
      (value "TLP521-1")
      (footprint "DIP4")
      (description "光耦")
      (libsource (lib "mylib") (part "TLP521"))
    )
    (comp (ref "U8")
      (value "TLP521-1")
      (footprint "DIP4")
      (description "光耦")
      (libsource (lib "mylib") (part "TLP521"))
    )
    (comp (ref "U9")
      (value "TLP521-1")
      (footprint "DIP4")
      (description "光耦")
      (libsource (lib "mylib") (part "TLP521"))
    )
    (comp (ref "U10")
      (value "TLP521-1")
      (footprint "DIP4")
      (description "光耦")
      (libsource (lib "mylib") (part "TLP521"))
    )
    (comp (ref "U11")
      (value "TLP521-1")
      (footprint "DIP4")
      (description "光耦")
      (libsource (lib "mylib") (part "TLP521"))
    )
    (comp (ref "U12")
      (value "TLP521-1")
      (footprint "DIP4")
      (description "光耦")
      (libsource (lib "mylib") (part "TLP521"))
    )
    (comp (ref "U13")
      (value "LM2596S_5.0")
      (footprint "TO-263-5")
      (description "3A开关电源芯片")
      (libsource (lib "Zhuangzaiji") (part "LM2596S_5.0"))
    )
    (comp (ref "U14") (value "TP4056") (footprint "SO8E") (libsource (lib "*") (part "TP4056")))
    (comp (ref "U15")
      (value "TLP521-1")
      (footprint "DIP4")
      (description "光耦")
      (libsource (lib "mylib") (part "TLP521"))
    )
    (comp (ref "U16")
      (value "TLP521-1")
      (footprint "DIP4")
      (description "光耦")
      (libsource (lib "mylib") (part "TLP521"))
    )
    (comp (ref "U17")
      (value "TLP521-1")
      (footprint "DIP4")
      (description "光耦")
      (libsource (lib "mylib") (part "TLP521"))
    )
    (comp (ref "U18")
      (value "TLP521-1")
      (footprint "DIP4")
      (description "光耦")
      (libsource (lib "mylib") (part "TLP521"))
    )
    (comp (ref "U19")
      (value "TLP521-1")
      (footprint "DIP4")
      (description "光耦")
      (libsource (lib "mylib") (part "TLP521"))
    )
    (comp (ref "U20")
      (value "TLP521-1")
      (footprint "DIP4")
      (description "光耦")
      (libsource (lib "mylib") (part "TLP521"))
    )
    (comp (ref "U21")
      (value "TLP521-1")
      (footprint "DIP4")
      (description "光耦")
      (libsource (lib "mylib") (part "TLP521"))
    )
    (comp (ref "U22")
      (value "TLP521-1")
      (footprint "DIP4")
      (description "光耦")
      (libsource (lib "mylib") (part "TLP521"))
    )
    (comp (ref "U23") (value "CH340") (footprint "SOP16") (libsource (lib "INSPUR_SCH") (part "CH340")))
    (comp (ref "U24")
      (value "ENC28J60")
      (footprint "ssop28")
      (libsource (lib "INSPUR_SCH") (part "ENC28J60"))
    )
    (comp (ref "U25") (value "SIM900") (footprint "SIM-900") (libsource (lib "ATK-SIM900A") (part "SIM900")))
    (comp (ref "U27")
      (value "SIM")
      (footprint "sim-6p")
      (description "手机SIM卡")
      (libsource (lib "ATK-SIM900A") (part "SIM"))
    )
    (comp (ref "U28") (value "SMF05") (footprint "SC70-6L") (libsource (lib "INSPUR_SCH") (part "SMF05")))
    (comp (ref "Y1")
      (value "8MHz")
      (footprint "XTAL_US")
      (description "Crystal Oscillator")
      (fields (field (name "PUBLISHER") "Altium Limited"))
      (libsource (lib "mylib") (part "XTAL"))
    )
    (comp (ref "Y2")
      (value "32.768KHz")
      (footprint "cs-308")
      (description "Crystal Oscillator")
      (fields (field (name "PUBLISHER") "Altium Limited"))
      (libsource (lib "mylib") (part "XTAL"))
    )
    (comp (ref "Y3")
      (value "32.768KHZ")
      (footprint "CS-308")
      (description "Crystal Oscillator")
      (fields (field (name "PUBLISHER") "Altium Limited"))
      (libsource (lib "mylib") (part "XTAL"))
    )
    (comp (ref "Y4") (value "25M") (footprint "XTAL_US") (libsource (lib "INSPUR_SCH") (part "CRYSTAL")))
    (comp (ref "Y5") (value "12M") (footprint "XTAL_US") (libsource (lib "INSPUR_SCH") (part "CRYSTAL")))
  )
  (nets
    (net (code "1") (name "/AD_IN1") (class "Default")
      (node (ref "R7") (pin "1") (pintype "passive"))
      (node (ref "R8") (pin "2") (pintype "passive"))
      (node (ref "U2") (pin "16") (pinfunction "PC1/ADC11_16") (pintype "bidirectional"))
    )
    (net (code "2") (name "/AD_IN2") (class "Default")
      (node (ref "R72") (pin "1") (pintype "passive"))
      (node (ref "R73") (pin "2") (pintype "passive"))
      (node (ref "U2") (pin "17") (pinfunction "PC2/ADC12_17") (pintype "bidirectional"))
    )
    (net (code "3") (name "/BEEP") (class "Default")
      (node (ref "R19") (pin "1") (pintype "passive"))
      (node (ref "U2") (pin "38") (pinfunction "PE7/TIM1_ETR_38") (pintype "bidirectional"))
    )
    (net (code "4") (name "/BOOT0") (class "Default")
      (node (ref "R85") (pin "1") (pinfunction "1_1") (pintype "passive"))
      (node (ref "R9") (pin "1") (pinfunction "1_1") (pintype "passive"))
      (node (ref "U2") (pin "94") (pinfunction "BOOT0_94") (pintype "input"))
    )
    (net (code "5") (name "/BOOT1") (class "Default")
      (node (ref "R2") (pin "1") (pinfunction "1_1") (pintype "passive"))
      (node (ref "U2") (pin "37") (pinfunction "PB2/BOOT1_37") (pintype "bidirectional"))
    )
    (net (code "6") (name "/CH340D+") (class "Default")
      (node (ref "R113") (pin "1") (pinfunction "1_1") (pintype "passive"))
      (node (ref "U23") (pin "5") (pinfunction "D+_5") (pintype "passive"))
    )
    (net (code "7") (name "/CH340D-") (class "Default")
      (node (ref "R111") (pin "1") (pinfunction "1_1") (pintype "passive"))
      (node (ref "U23") (pin "6") (pinfunction "D-_6") (pintype "passive"))
    )
    (net (code "8") (name "/CPU_IN1") (class "Default")
      (node (ref "R43") (pin "1") (pintype "passive"))
      (node (ref "U2") (pin "78") (pinfunction "PC10/USART3_TX_78") (pintype "bidirectional"))
      (node (ref "U5") (pin "4") (pinfunction "4_4") (pintype "passive"))
    )
    (net (code "9") (name "/CPU_IN2") (class "Default")
      (node (ref "R44") (pin "1") (pintype "passive"))
      (node (ref "U2") (pin "79") (pinfunction "PC11/USART3_RX_79") (pintype "bidirectional"))
      (node (ref "U6") (pin "4") (pinfunction "4_4") (pintype "passive"))
    )
    (net (code "10") (name "/CPU_IN3") (class "Default")
      (node (ref "R45") (pin "1") (pintype "passive"))
      (node (ref "U2") (pin "80") (pinfunction "PC12/USART3_CK_80") (pintype "bidirectional"))
      (node (ref "U7") (pin "4") (pinfunction "4_4") (pintype "passive"))
    )
    (net (code "11") (name "/CPU_IN4") (class "Default")
      (node (ref "R46") (pin "1") (pintype "passive"))
      (node (ref "U2") (pin "81") (pinfunction "PD0/OSC_IN/CAN_RX_81") (pintype "bidirectional"))
      (node (ref "U8") (pin "4") (pinfunction "4_4") (pintype "passive"))
    )
    (net (code "12") (name "/CPU_IN5") (class "Default")
      (node (ref "R47") (pin "1") (pintype "passive"))
      (node (ref "U2") (pin "82") (pinfunction "PD1/OSC_OUT/CAN_TX_82") (pintype "bidirectional"))
      (node (ref "U9") (pin "4") (pinfunction "4_4") (pintype "passive"))
    )
    (net (code "13") (name "/CPU_IN6") (class "Default")
      (node (ref "R48") (pin "1") (pintype "passive"))
      (node (ref "U10") (pin "4") (pinfunction "4_4") (pintype "passive"))
      (node (ref "U2") (pin "83") (pinfunction "PD2/TIM3_ETR_83") (pintype "bidirectional"))
    )
    (net (code "14") (name "/CPU_IN7") (class "Default")
      (node (ref "R49") (pin "1") (pintype "passive"))
      (node (ref "U11") (pin "4") (pinfunction "4_4") (pintype "passive"))
      (node (ref "U2") (pin "84") (pinfunction "PD3/USART2_CTS_84") (pintype "bidirectional"))
    )
    (net (code "15") (name "/CPU_IN8") (class "Default")
      (node (ref "R50") (pin "1") (pintype "passive"))
      (node (ref "U12") (pin "4") (pinfunction "4_4") (pintype "passive"))
      (node (ref "U2") (pin "85") (pinfunction "PD4/USART2_RTS_85") (pintype "bidirectional"))
    )
    (net (code "16") (name "/CPU_IN9") (class "Default")
      (node (ref "R74") (pin "1") (pintype "passive"))
      (node (ref "U15") (pin "4") (pinfunction "4_4") (pintype "passive"))
      (node (ref "U2") (pin "86") (pinfunction "PD5/USART2_TX_86") (pintype "bidirectional"))
    )
    (net (code "17") (name "/CPU_IN10") (class "Default")
      (node (ref "R75") (pin "1") (pintype "passive"))
      (node (ref "U16") (pin "4") (pinfunction "4_4") (pintype "passive"))
      (node (ref "U2") (pin "87") (pinfunction "PD6/USART2_RX_87") (pintype "bidirectional"))
    )
    (net (code "18") (name "/CPU_IN11") (class "Default")
      (node (ref "R76") (pin "1") (pintype "passive"))
      (node (ref "U17") (pin "4") (pinfunction "4_4") (pintype "passive"))
      (node (ref "U2") (pin "88") (pinfunction "PD7/USART2_CK_88") (pintype "bidirectional"))
    )
    (net (code "19") (name "/CPU_IN12") (class "Default")
      (node (ref "R77") (pin "1") (pintype "passive"))
      (node (ref "U18") (pin "4") (pinfunction "4_4") (pintype "passive"))
      (node (ref "U2") (pin "91") (pinfunction "PB5/I2C1_SMBAI/TIM3_CH2/SPI1_MOSI_91") (pintype "bidirectional"))
    )
    (net (code "20") (name "/CPU_IN13") (class "Default")
      (node (ref "R78") (pin "1") (pintype "passive"))
      (node (ref "U19") (pin "4") (pinfunction "4_4") (pintype "passive"))
      (node (ref "U2") (pin "95") (pinfunction "PB8/TIM4_CH3/I2C1_SCL/CAN_RX_95") (pintype "bidirectional"))
    )
    (net (code "21") (name "/CPU_IN14") (class "Default")
      (node (ref "R79") (pin "1") (pintype "passive"))
      (node (ref "U2") (pin "96") (pinfunction "PB9/TIM4_CH4/I2C1_SDA/CAN_TX_96") (pintype "bidirectional"))
      (node (ref "U20") (pin "4") (pinfunction "4_4") (pintype "passive"))
    )
    (net (code "22") (name "/CPU_IN15") (class "Default")
      (node (ref "R80") (pin "1") (pintype "passive"))
      (node (ref "U2") (pin "97") (pinfunction "PE0/TIM4_ETR_97") (pintype "bidirectional"))
      (node (ref "U21") (pin "4") (pinfunction "4_4") (pintype "passive"))
    )
    (net (code "23") (name "/CPU_IN16") (class "Default")
      (node (ref "R81") (pin "1") (pintype "passive"))
      (node (ref "U2") (pin "98") (pinfunction "PE1_98") (pintype "bidirectional"))
      (node (ref "U22") (pin "4") (pinfunction "4_4") (pintype "passive"))
    )
    (net (code "24") (name "/CPU_JDQ1") (class "Default")
      (node (ref "C65") (pin "1") (pinfunction "1_1") (pintype "passive"))
      (node (ref "Q9") (pin "1") (pinfunction "B_1") (pintype "input"))
      (node (ref "R99") (pin "2") (pintype "passive"))
      (node (ref "U2") (pin "63") (pinfunction "PC6/TIM3_CH1_63") (pintype "bidirectional"))
    )
    (net (code "25") (name "/CPU_JDQ2") (class "Default")
      (node (ref "C66") (pin "1") (pinfunction "1_1") (pintype "passive"))
      (node (ref "Q10") (pin "1") (pinfunction "B_1") (pintype "input"))
      (node (ref "R101") (pin "2") (pintype "passive"))
      (node (ref "U2") (pin "64") (pinfunction "PC7/TIM3_CH2_64") (pintype "bidirectional"))
    )
    (net (code "26") (name "/CPU_JDQ3") (class "Default")
      (node (ref "C67") (pin "1") (pinfunction "1_1") (pintype "passive"))
      (node (ref "Q11") (pin "1") (pinfunction "B_1") (pintype "input"))
      (node (ref "R102") (pin "2") (pintype "passive"))
      (node (ref "U2") (pin "65") (pinfunction "PC8/TIM3_CH3_65") (pintype "bidirectional"))
    )
    (net (code "27") (name "/CPU_JDQ4") (class "Default")
      (node (ref "C68") (pin "1") (pinfunction "1_1") (pintype "passive"))
      (node (ref "Q12") (pin "1") (pinfunction "B_1") (pintype "input"))
      (node (ref "R104") (pin "2") (pintype "passive"))
      (node (ref "U2") (pin "66") (pinfunction "PC9/TIM3_CH4_66") (pintype "bidirectional"))
    )
    (net (code "28") (name "/DS_IO") (class "Default")
      (node (ref "U2") (pin "58") (pinfunction "PD11/USART3_CTS_58") (pintype "bidirectional"))
      (node (ref "U4") (pin "6") (pinfunction "I/O_6") (pintype "bidirectional"))
    )
    (net (code "29") (name "/DS_RST") (class "Default")
      (node (ref "U2") (pin "59") (pinfunction "PD12/TIM4_CH1/USART3_RTS_59") (pintype "bidirectional"))
      (node (ref "U4") (pin "5") (pinfunction "~{RST}_5") (pintype "input"))
    )
    (net (code "30") (name "/DS_SCLK") (class "Default")
      (node (ref "U2") (pin "57") (pinfunction "PD10/USART3_CK_57") (pintype "bidirectional"))
      (node (ref "U4") (pin "7") (pinfunction "SCLK_7") (pintype "input"))
    )
    (net (code "31") (name "/I2C1_SCL") (class "Default")
      (node (ref "R23") (pin "1") (pintype "passive"))
      (node (ref "U2") (pin "92") (pinfunction "PB6/I2C1_SCL/TIM4_CH1/USART1_TX_92") (pintype "bidirectional"))
      (node (ref "U3") (pin "6") (pinfunction "SCL_6") (pintype "passive"))
    )
    (net (code "32") (name "/I2C1_SDA") (class "Default")
      (node (ref "R24") (pin "1") (pintype "passive"))
      (node (ref "U2") (pin "93") (pinfunction "PB7/I2C1_SDA/TIM4_CH2/USART1_RX_93") (pintype "bidirectional"))
      (node (ref "U3") (pin "5") (pinfunction "SDA_5") (pintype "passive"))
    )
    (net (code "33") (name "/IN1") (class "Default")
      (node (ref "J2") (pin "1") (pinfunction "1_1") (pintype "passive"))
      (node (ref "R25") (pin "1") (pintype "passive"))
    )
    (net (code "34") (name "/IN2") (class "Default")
      (node (ref "J2") (pin "2") (pinfunction "2_2") (pintype "passive"))
      (node (ref "R26") (pin "1") (pintype "passive"))
    )
    (net (code "35") (name "/IN3") (class "Default")
      (node (ref "J2") (pin "3") (pinfunction "3_3") (pintype "passive"))
      (node (ref "R27") (pin "1") (pintype "passive"))
    )
    (net (code "36") (name "/IN4") (class "Default")
      (node (ref "J2") (pin "4") (pinfunction "4_4") (pintype "passive"))
      (node (ref "R28") (pin "1") (pintype "passive"))
    )
    (net (code "37") (name "/IN5") (class "Default")
      (node (ref "J2") (pin "5") (pinfunction "5_5") (pintype "passive"))
      (node (ref "R29") (pin "1") (pintype "passive"))
    )
    (net (code "38") (name "/IN6") (class "Default")
      (node (ref "J2") (pin "6") (pinfunction "6_6") (pintype "passive"))
      (node (ref "R30") (pin "1") (pintype "passive"))
    )
    (net (code "39") (name "/IN7") (class "Default")
      (node (ref "J2") (pin "7") (pinfunction "7_7") (pintype "passive"))
      (node (ref "R31") (pin "1") (pintype "passive"))
    )
    (net (code "40") (name "/IN8") (class "Default")
      (node (ref "J2") (pin "8") (pinfunction "8_8") (pintype "passive"))
      (node (ref "R32") (pin "1") (pintype "passive"))
    )
    (net (code "41") (name "/IN9") (class "Default")
      (node (ref "J3") (pin "1") (pinfunction "1_1") (pintype "passive"))
      (node (ref "R54") (pin "1") (pintype "passive"))
    )
    (net (code "42") (name "/IN10") (class "Default")
      (node (ref "J3") (pin "2") (pinfunction "2_2") (pintype "passive"))
      (node (ref "R55") (pin "1") (pintype "passive"))
    )
    (net (code "43") (name "/IN11") (class "Default")
      (node (ref "J3") (pin "3") (pinfunction "3_3") (pintype "passive"))
      (node (ref "R56") (pin "1") (pintype "passive"))
    )
    (net (code "44") (name "/IN12") (class "Default")
      (node (ref "J3") (pin "4") (pinfunction "4_4") (pintype "passive"))
      (node (ref "R57") (pin "1") (pintype "passive"))
    )
    (net (code "45") (name "/IN13") (class "Default")
      (node (ref "J3") (pin "5") (pinfunction "5_5") (pintype "passive"))
      (node (ref "R58") (pin "1") (pintype "passive"))
    )
    (net (code "46") (name "/IN14") (class "Default")
      (node (ref "J3") (pin "6") (pinfunction "6_6") (pintype "passive"))
      (node (ref "R59") (pin "1") (pintype "passive"))
    )
    (net (code "47") (name "/IN15") (class "Default")
      (node (ref "J3") (pin "7") (pinfunction "7_7") (pintype "passive"))
      (node (ref "R60") (pin "1") (pintype "passive"))
    )
    (net (code "48") (name "/IN16") (class "Default")
      (node (ref "J3") (pin "8") (pinfunction "8_8") (pintype "passive"))
      (node (ref "R61") (pin "1") (pintype "passive"))
    )
    (net (code "49") (name "/JDQOUT1") (class "Default")
      (node (ref "D28") (pin "1") (pintype "passive"))
      (node (ref "K5") (pin "3") (pinfunction "3_3") (pintype "passive"))
      (node (ref "Q9") (pin "3") (pinfunction "C_3") (pintype "passive"))
    )
    (net (code "50") (name "/JDQOUT2") (class "Default")
      (node (ref "D29") (pin "1") (pintype "passive"))
      (node (ref "K6") (pin "3") (pinfunction "3_3") (pintype "passive"))
      (node (ref "Q10") (pin "3") (pinfunction "C_3") (pintype "passive"))
    )
    (net (code "51") (name "/JDQOUT3") (class "Default")
      (node (ref "D30") (pin "1") (pintype "passive"))
      (node (ref "K7") (pin "3") (pinfunction "3_3") (pintype "passive"))
      (node (ref "Q11") (pin "3") (pinfunction "C_3") (pintype "passive"))
    )
    (net (code "52") (name "/JDQOUT4") (class "Default")
      (node (ref "D31") (pin "1") (pintype "passive"))
      (node (ref "K8") (pin "3") (pinfunction "3_3") (pintype "passive"))
      (node (ref "Q12") (pin "3") (pinfunction "C_3") (pintype "passive"))
    )
    (net (code "53") (name "/JTCK") (class "Default")
      (node (ref "JTAG_1") (pin "9") (pinfunction "TCK/SWCLK_9") (pintype "passive"))
      (node (ref "R6") (pin "1") (pintype "passive"))
      (node (ref "U2") (pin "76") (pinfunction "PA14/JTCK/SWCLK_76") (pintype "bidirectional"))
    )
    (net (code "54") (name "/JTDI") (class "Default")
      (node (ref "JTAG_1") (pin "5") (pinfunction "TDI_5") (pintype "passive"))
      (node (ref "R4") (pin "2") (pintype "passive"))
      (node (ref "U2") (pin "77") (pinfunction "PA15/JTDI_77") (pintype "bidirectional"))
    )
    (net (code "55") (name "/JTDO") (class "Default")
      (node (ref "JTAG_1") (pin "6") (pinfunction "TDO/SWO_6") (pintype "passive"))
      (node (ref "R22") (pin "2") (pintype "passive"))
      (node (ref "U2") (pin "89") (pinfunction "PB3/JTDO_89") (pintype "bidirectional"))
    )
    (net (code "56") (name "/JTMS") (class "Default")
      (node (ref "JTAG_1") (pin "7") (pinfunction "TMS/SWDIO_7") (pintype "passive"))
      (node (ref "R5") (pin "2") (pintype "passive"))
      (node (ref "U2") (pin "72") (pinfunction "PA13/JTMS/SWDIO_72") (pintype "bidirectional"))
    )
    (net (code "57") (name "/JTRST") (class "Default")
      (node (ref "JTAG_1") (pin "3") (pinfunction "NTRST_3") (pintype "passive"))
      (node (ref "R3") (pin "2") (pintype "passive"))
      (node (ref "U2") (pin "90") (pinfunction "PB4/JNTRST_90") (pintype "bidirectional"))
    )
    (net (code "58") (name "/KEY0") (class "Default")
      (node (ref "K1") (pin "2") (pinfunction "2_2") (pintype "passive"))
      (node (ref "U2") (pin "1") (pinfunction "PE2_1") (pintype "bidirectional"))
    )
    (net (code "59") (name "/KEY1") (class "Default")
      (node (ref "K2") (pin "2") (pinfunction "2_2") (pintype "passive"))
      (node (ref "U2") (pin "2") (pinfunction "PE3_2") (pintype "bidirectional"))
    )
    (net (code "60") (name "/KEY2") (class "Default")
      (node (ref "K3") (pin "2") (pinfunction "2_2") (pintype "passive"))
      (node (ref "U2") (pin "3") (pinfunction "PE4_3") (pintype "bidirectional"))
    )
    (net (code "61") (name "/KEY3") (class "Default")
      (node (ref "K4") (pin "2") (pinfunction "2_2") (pintype "passive"))
      (node (ref "U2") (pin "4") (pinfunction "PE5_4") (pintype "bidirectional"))
    )
    (net (code "62") (name "/LED0_0") (class "Default")
      (node (ref "R10") (pin "2") (pintype "passive"))
      (node (ref "U2") (pin "39") (pinfunction "PE8/TIM1_CH1N_39") (pintype "bidirectional"))
    )
    (net (code "63") (name "/LED0_1") (class "Default")
      (node (ref "R11") (pin "2") (pintype "passive"))
      (node (ref "U2") (pin "40") (pinfunction "PE9/TIM1_CH1_40") (pintype "bidirectional"))
    )
    (net (code "64") (name "/LED1_0") (class "Default")
      (node (ref "R12") (pin "2") (pintype "passive"))
      (node (ref "U2") (pin "41") (pinfunction "PE10/TIM1_CH2N_41") (pintype "bidirectional"))
    )
    (net (code "65") (name "/LED1_1") (class "Default")
      (node (ref "R13") (pin "2") (pintype "passive"))
      (node (ref "U2") (pin "42") (pinfunction "PE11/TIM1_CH2_42") (pintype "bidirectional"))
    )
    (net (code "66") (name "/LED2_0") (class "Default")
      (node (ref "R14") (pin "2") (pintype "passive"))
      (node (ref "U2") (pin "43") (pinfunction "PE12/TIM1_CH3N_43") (pintype "bidirectional"))
    )
    (net (code "67") (name "/LED2_1") (class "Default")
      (node (ref "R15") (pin "2") (pintype "passive"))
      (node (ref "U2") (pin "44") (pinfunction "PE13/TIM1_CH3_44") (pintype "bidirectional"))
    )
    (net (code "68") (name "/LED3_0") (class "Default")
      (node (ref "R16") (pin "2") (pintype "passive"))
      (node (ref "U2") (pin "45") (pinfunction "PE14/TIM1_CH4_45") (pintype "bidirectional"))
    )
    (net (code "69") (name "/LED3_1") (class "Default")
      (node (ref "R17") (pin "2") (pintype "passive"))
      (node (ref "U2") (pin "46") (pinfunction "PE15/TIM1_BKIN_46") (pintype "bidirectional"))
    )
    (net (code "70") (name "/NET_CS") (class "Default")
      (node (ref "R94") (pin "2") (pinfunction "2_2") (pintype "passive"))
      (node (ref "U2") (pin "29") (pinfunction "PA4/SPI1_NSS/USART2_CK/ADC4_29") (pintype "bidirectional"))
    )
    (net (code "71") (name "/NET_INT") (class "Default")
      (node (ref "U2") (pin "24") (pinfunction "PA1/USART2_RTS/ADC1/TIM2_CH2_24") (pintype "bidirectional"))
      (node (ref "U24") (pin "4") (pinfunction "INT_4") (pintype "passive"))
    )
    (net (code "72") (name "/NET_RST") (class "Default")
      (node (ref "U2") (pin "23") (pinfunction "PA0-WKUP/USART2_CTS/ADC0/TIM2_CH1_ETR_23") (pintype "bidirectional"))
      (node (ref "U24") (pin "10") (pinfunction "RESET_10") (pintype "passive"))
    )
    (net (code "73") (name "/OSC32_IN") (class "Default")
      (node (ref "C11") (pin "2") (pintype "passive"))
      (node (ref "U2") (pin "8") (pinfunction "PC14-OSC32_IN_8") (pintype "bidirectional"))
      (node (ref "Y3") (pin "2") (pinfunction "OSC2_2") (pintype "passive"))
    )
    (net (code "74") (name "/OSC32_OUT") (class "Default")
      (node (ref "C12") (pin "2") (pintype "passive"))
      (node (ref "U2") (pin "9") (pinfunction "PC15-OSC32_OUT_9") (pintype "bidirectional"))
      (node (ref "Y3") (pin "1") (pinfunction "OSC1_1") (pintype "passive"))
    )
    (net (code "75") (name "/OSC_IN") (class "Default")
      (node (ref "C1") (pin "1") (pintype "passive"))
      (node (ref "R1") (pin "1") (pintype "passive"))
      (node (ref "U2") (pin "12") (pinfunction "OSC_IN_12") (pintype "input"))
      (node (ref "Y1") (pin "1") (pinfunction "OSC1_1") (pintype "passive"))
    )
    (net (code "76") (name "/OSC_OUT") (class "Default")
      (node (ref "C2") (pin "1") (pintype "passive"))
      (node (ref "R1") (pin "2") (pintype "passive"))
      (node (ref "U2") (pin "13") (pinfunction "OSC_OUT_13") (pintype "output"))
      (node (ref "Y1") (pin "2") (pinfunction "OSC2_2") (pintype "passive"))
    )
    (net (code "77") (name "/PWRKEY") (class "Default")
      (node (ref "Q7") (pin "3") (pinfunction "C_3") (pintype "passive"))
      (node (ref "U25") (pin "1") (pinfunction "PWRKEY_1") (pintype "passive"))
    )
    (net (code "78") (name "/RESET") (class "Default")
      (node (ref "C7") (pin "2") (pintype "passive"))
      (node (ref "D24") (pin "1") (pinfunction "A_1") (pintype "passive"))
      (node (ref "JTAG_1") (pin "4") (pinfunction "NRST_4") (pintype "passive"))
      (node (ref "R18") (pin "1") (pintype "passive"))
      (node (ref "U2") (pin "14") (pinfunction "NRST_14") (pintype "bidirectional"))
    )
    (net (code "79") (name "/SIM900_RST") (class "Default")
      (node (ref "R87") (pin "1") (pintype "passive"))
      (node (ref "U2") (pin "67") (pinfunction "PA8/USART1_CK/TIM1_CH1/MCO_67") (pintype "bidirectional"))
    )
    (net (code "80") (name "/SIM900_RXD") (class "Default")
      (node (ref "U2") (pin "68") (pinfunction "PA9/USART1_TX/TIM1_CH2_68") (pintype "bidirectional"))
      (node (ref "U25") (pin "10") (pinfunction "RXD_I_10") (pintype "passive"))
    )
    (net (code "81") (name "/SIM900_TXD") (class "Default")
      (node (ref "U2") (pin "69") (pinfunction "PA10/USART1_RX/TIM1_CH3_69") (pintype "bidirectional"))
      (node (ref "U25") (pin "9") (pinfunction "TXD_O_9") (pintype "passive"))
    )
    (net (code "82") (name "/SIM_CLK") (class "Default")
      (node (ref "R116") (pin "2") (pinfunction "2_2") (pintype "passive"))
      (node (ref "U25") (pin "32") (pinfunction "SIM_CLK_32") (pintype "passive"))
    )
    (net (code "83") (name "/SIM_DATA") (class "Default")
      (node (ref "R118") (pin "2") (pinfunction "2_2") (pintype "passive"))
      (node (ref "U25") (pin "31") (pinfunction "SIM_DATA_31") (pintype "passive"))
    )
    (net (code "84") (name "/SIM_PWRKEY") (class "Default")
      (node (ref "R91") (pin "1") (pintype "passive"))
      (node (ref "U2") (pin "70") (pinfunction "PA11/USART1_CTS/USBDM/CAN_RX/TIM1_CH4_70") (pintype "bidirectional"))
    )
    (net (code "85") (name "/SIM_RST") (class "Default")
      (node (ref "R117") (pin "2") (pinfunction "2_2") (pintype "passive"))
      (node (ref "U25") (pin "33") (pinfunction "SIM_RST_33") (pintype "passive"))
    )
    (net (code "86") (name "/SIM_VDD") (class "Default")
      (node (ref "U25") (pin "30") (pinfunction "SIM_VDD_30") (pintype "passive"))
      (node (ref "U27") (pin "6") (pinfunction "VCC_6") (pintype "passive"))
      (node (ref "U28") (pin "4") (pintype "passive"))
    )
    (net (code "87") (name "/SPI2_MISO") (class "Default")
      (node (ref "U2") (pin "31") (pinfunction "PA6/SPI1_MISO/ADC6/TIM3_CH1/TIM1_BKIN_31") (pintype "bidirectional"))
      (node (ref "U24") (pin "6") (pinfunction "SO_6") (pintype "passive"))
    )
    (net (code "88") (name "/SPI2_MOSI") (class "Default")
      (node (ref "U2") (pin "32") (pinfunction "PA7/SPI1_MOSI/ADC7/TIM3_CH2/TIM1_CH1N_32") (pintype "bidirectional"))
      (node (ref "U24") (pin "7") (pinfunction "SI_7") (pintype "passive"))
    )
    (net (code "89") (name "/SPI2_SCK") (class "Default")
      (node (ref "U2") (pin "30") (pinfunction "PA5/SPI1_SCK/ADC5_30") (pintype "bidirectional"))
      (node (ref "U24") (pin "8") (pinfunction "SCK_8") (pintype "passive"))
    )
    (net (code "90") (name "/SR") (class "Default") (node (ref "U14") (pin "9") (pintype "passive")))
    (net (code "91") (name "/USART2_RX") (class "Default")
      (node (ref "U2") (pin "26") (pinfunction "PA3/USART2_RX/ADC3/TIM2_CH4_26") (pintype "bidirectional"))
      (node (ref "U23") (pin "2") (pinfunction "TXD_2") (pintype "passive"))
    )
    (net (code "92") (name "/USART2_TX") (class "Default")
      (node (ref "U2") (pin "25") (pinfunction "PA2/USART2_TX/ADC2/TIM2_CH3_25") (pintype "bidirectional"))
      (node (ref "U23") (pin "3") (pinfunction "RXD_3") (pintype "passive"))
    )
    (net (code "93") (name "/USART3_RX") (class "Default")
      (node (ref "U2") (pin "48") (pinfunction "PB11/I2C2_SDA/USART3_RX/TIM2_CH4_48") (pintype "bidirectional"))
    )
    (net (code "94") (name "/USART3_TX") (class "Default")
      (node (ref "U2") (pin "47") (pinfunction "PB10/I2C2_SCL/USART3_TX/TIM2_CH3_47") (pintype "bidirectional"))
    )
    (net (code "95") (name "/WOL") (class "Default")
      (node (ref "U2") (pin "15") (pinfunction "PC0/AD10_15") (pintype "bidirectional"))
      (node (ref "U24") (pin "5") (pinfunction "WOL_5") (pintype "passive"))
    )
    (net (code "96") (name "GND") (class "Default")
      (node (ref "BAT1") (pin "2") (pinfunction "GND_2") (pintype "passive"))
      (node (ref "C1") (pin "2") (pintype "passive"))
      (node (ref "C10") (pin "2") (pintype "passive"))
      (node (ref "C11") (pin "1") (pintype "passive"))
      (node (ref "C12") (pin "1") (pintype "passive"))
      (node (ref "C13") (pin "2") (pinfunction "GND_2") (pintype "passive"))
      (node (ref "C14") (pin "1") (pintype "passive"))
      (node (ref "C15") (pin "2") (pinfunction "2_2") (pintype "passive"))
      (node (ref "C16") (pin "2") (pinfunction "2_2") (pintype "passive"))
      (node (ref "C17") (pin "2") (pinfunction "GND_2") (pintype "passive"))
      (node (ref "C18") (pin "1") (pintype "passive"))
      (node (ref "C19") (pin "2") (pinfunction "2_2") (pintype "passive"))
      (node (ref "C2") (pin "2") (pintype "passive"))
      (node (ref "C20") (pin "1") (pinfunction "1_1") (pintype "passive"))
      (node (ref "C21") (pin "1") (pinfunction "1_1") (pintype "passive"))
      (node (ref "C22") (pin "2") (pinfunction "2_2") (pintype "passive"))
      (node (ref "C23") (pin "1") (pinfunction "1_1") (pintype "passive"))
      (node (ref "C24") (pin "2") (pinfunction "2_2") (pintype "passive"))
      (node (ref "C25") (pin "2") (pinfunction "2_2") (pintype "passive"))
      (node (ref "C26") (pin "2") (pinfunction "2_2") (pintype "passive"))
      (node (ref "C27") (pin "2") (pinfunction "2_2") (pintype "passive"))
      (node (ref "C28") (pin "2") (pinfunction "2_2") (pintype "passive"))
      (node (ref "C29") (pin "2") (pinfunction "2_2") (pintype "passive"))
      (node (ref "C3") (pin "1") (pintype "passive"))
      (node (ref "C30") (pin "1") (pinfunction "1_1") (pintype "passive"))
      (node (ref "C31") (pin "1") (pinfunction "1_1") (pintype "passive"))
      (node (ref "C32") (pin "1") (pintype "passive"))
      (node (ref "C33") (pin "2") (pintype "passive"))
      (node (ref "C34") (pin "1") (pinfunction "1_1") (pintype "passive"))
      (node (ref "C35") (pin "2") (pinfunction "GND_2") (pintype "passive"))
      (node (ref "C36") (pin "2") (pintype "passive"))
      (node (ref "C37") (pin "2") (pinfunction "GND_2") (pintype "passive"))
      (node (ref "C38") (pin "2") (pintype "passive"))
      (node (ref "C39") (pin "1") (pinfunction "1_1") (pintype "passive"))
      (node (ref "C4") (pin "1") (pintype "passive"))
      (node (ref "C40") (pin "2") (pinfunction "2_2") (pintype "passive"))
      (node (ref "C41") (pin "2") (pinfunction "2_2") (pintype "passive"))
      (node (ref "C42") (pin "2") (pinfunction "2_2") (pintype "passive"))
      (node (ref "C43") (pin "2") (pinfunction "2_2") (pintype "passive"))
      (node (ref "C65") (pin "2") (pinfunction "2_2") (pintype "passive"))
      (node (ref "C66") (pin "2") (pinfunction "2_2") (pintype "passive"))
      (node (ref "C67") (pin "2") (pinfunction "2_2") (pintype "passive"))
      (node (ref "C68") (pin "2") (pinfunction "2_2") (pintype "passive"))
      (node (ref "C69") (pin "1") (pinfunction "1_1") (pintype "passive"))
      (node (ref "C7") (pin "1") (pintype "passive"))
      (node (ref "C70") (pin "1") (pinfunction "1_1") (pintype "passive"))
      (node (ref "C71") (pin "1") (pinfunction "1_1") (pintype "passive"))
      (node (ref "C72") (pin "1") (pinfunction "1_1") (pintype "passive"))
      (node (ref "C73") (pin "1") (pinfunction "1_1") (pintype "passive"))
      (node (ref "C9") (pin "2") (pintype "passive"))
      (node (ref "D12") (pin "1") (pinfunction "A_1") (pintype "passive"))
      (node (ref "D25") (pin "2") (pintype "passive"))
      (node (ref "D26") (pin "2") (pintype "passive"))
      (node (ref "D27") (pin "2") (pintype "passive"))
      (node (ref "J1") (pin "2") (pintype "passive"))
      (node (ref "J1") (pin "3") (pintype "passive"))
      (node (ref "J4") (pin "2") (pinfunction "2_2") (pintype "passive"))
      (node (ref "J5") (pin "5") (pinfunction "GNG_5") (pintype "passive"))
      (node (ref "J6") (pin "10") (pinfunction "L-_10") (pintype "passive"))
      (node (ref "J6") (pin "11") (pinfunction "R-_11") (pintype "passive"))
      (node (ref "J6") (pin "13") (pinfunction "13_13") (pintype "passive"))
      (node (ref "J6") (pin "14") (pinfunction "14_14") (pintype "passive"))
      (node (ref "J6") (pin "8") (pinfunction "8_8") (pintype "passive"))
      (node (ref "JTAG_1") (pin "10") (pinfunction "GND_10") (pintype "passive"))
      (node (ref "K1") (pin "1") (pinfunction "1_1") (pintype "passive"))
      (node (ref "K2") (pin "1") (pinfunction "1_1") (pintype "passive"))
      (node (ref "K3") (pin "1") (pinfunction "1_1") (pintype "passive"))
      (node (ref "K4") (pin "1") (pinfunction "1_1") (pintype "passive"))
      (node (ref "L1") (pin "1") (pinfunction "1_1") (pintype "passive"))
      (node (ref "L4") (pin "1") (pinfunction "1_1") (pintype "passive"))
      (node (ref "LED5") (pin "2") (pintype "passive"))
      (node (ref "P1") (pin "2") (pinfunction "GND_2") (pintype "power_in"))
      (node (ref "Q1") (pin "1") (pinfunction "E_1") (pintype "passive"))
      (node (ref "Q10") (pin "2") (pinfunction "E_2") (pintype "passive"))
      (node (ref "Q11") (pin "2") (pinfunction "E_2") (pintype "passive"))
      (node (ref "Q12") (pin "2") (pinfunction "E_2") (pintype "passive"))
      (node (ref "Q3") (pin "1") (pinfunction "E_1") (pintype "passive"))
      (node (ref "Q7") (pin "1") (pinfunction "E_1") (pintype "passive"))
      (node (ref "Q8") (pin "1") (pinfunction "E_1") (pintype "passive"))
      (node (ref "Q9") (pin "2") (pinfunction "E_2") (pintype "passive"))
      (node (ref "R2") (pin "2") (pinfunction "2_2") (pintype "passive"))
      (node (ref "R21") (pin "1") (pintype "passive"))
      (node (ref "R52") (pin "2") (pinfunction "2_2") (pintype "passive"))
      (node (ref "R53") (pin "2") (pinfunction "2_2") (pintype "passive"))
      (node (ref "R6") (pin "2") (pintype "passive"))
      (node (ref "R73") (pin "1") (pintype "passive"))
      (node (ref "R8") (pin "1") (pintype "passive"))
      (node (ref "R82") (pin "1") (pinfunction "1_1") (pintype "passive"))
      (node (ref "R83") (pin "1") (pinfunction "1_1") (pintype "passive"))
      (node (ref "R9") (pin "2") (pinfunction "2_2") (pintype "passive"))
      (node (ref "R90") (pin "2") (pinfunction "2_2") (pintype "passive"))
      (node (ref "R92") (pin "1") (pintype "passive"))
      (node (ref "R93") (pin "1") (pintype "passive"))
      (node (ref "U10") (pin "3") (pinfunction "3_3") (pintype "passive"))
      (node (ref "U11") (pin "3") (pinfunction "3_3") (pintype "passive"))
      (node (ref "U12") (pin "3") (pinfunction "3_3") (pintype "passive"))
      (node (ref "U13") (pin "3") (pinfunction "GND_3") (pintype "passive"))
      (node (ref "U13") (pin "5") (pinfunction "~{ON}/OFF_5") (pintype "passive"))
      (node (ref "U13") (pin "6") (pinfunction "TAB_6") (pintype "passive"))
      (node (ref "U14") (pin "1") (pinfunction "TEMP_1") (pintype "passive"))
      (node (ref "U14") (pin "3") (pinfunction "GND_3") (pintype "passive"))
      (node (ref "U15") (pin "3") (pinfunction "3_3") (pintype "passive"))
      (node (ref "U16") (pin "3") (pinfunction "3_3") (pintype "passive"))
      (node (ref "U17") (pin "3") (pinfunction "3_3") (pintype "passive"))
      (node (ref "U18") (pin "3") (pinfunction "3_3") (pintype "passive"))
      (node (ref "U19") (pin "3") (pinfunction "3_3") (pintype "passive"))
      (node (ref "U2") (pin "10") (pinfunction "VSS_5_10") (pintype "power_in"))
      (node (ref "U2") (pin "27") (pinfunction "VSS_4_27") (pintype "power_in"))
      (node (ref "U2") (pin "49") (pinfunction "VSS_1_49") (pintype "power_in"))
      (node (ref "U2") (pin "74") (pinfunction "VSS_2_74") (pintype "power_in"))
      (node (ref "U2") (pin "99") (pinfunction "VSS_3_99") (pintype "power_in"))
      (node (ref "U20") (pin "3") (pinfunction "3_3") (pintype "passive"))
      (node (ref "U21") (pin "3") (pinfunction "3_3") (pintype "passive"))
      (node (ref "U22") (pin "3") (pinfunction "3_3") (pintype "passive"))
      (node (ref "U23") (pin "1") (pinfunction "GND_1") (pintype "passive"))
      (node (ref "U24") (pin "11") (pinfunction "VSSRX_11") (pintype "passive"))
      (node (ref "U24") (pin "18") (pinfunction "VSSTX_18") (pintype "passive"))
      (node (ref "U24") (pin "2") (pinfunction "VSS_2") (pintype "passive"))
      (node (ref "U24") (pin "21") (pinfunction "VSSPLL_21") (pintype "passive"))
      (node (ref "U24") (pin "22") (pinfunction "VSSOSC_22") (pintype "passive"))
      (node (ref "U25") (pin "18") (pinfunction "GND_18") (pintype "passive"))
      (node (ref "U25") (pin "29") (pinfunction "GND_29") (pintype "passive"))
      (node (ref "U25") (pin "39") (pinfunction "GND_39") (pintype "passive"))
      (node (ref "U25") (pin "45") (pinfunction "GND_45") (pintype "passive"))
      (node (ref "U25") (pin "46") (pinfunction "GND_46") (pintype "passive"))
      (node (ref "U25") (pin "53") (pinfunction "GND_53") (pintype "passive"))
      (node (ref "U25") (pin "54") (pinfunction "GND_54") (pintype "passive"))
      (node (ref "U25") (pin "58") (pinfunction "GND_58") (pintype "passive"))
      (node (ref "U25") (pin "59") (pinfunction "GND_59") (pintype "passive"))
      (node (ref "U25") (pin "61") (pinfunction "GND_61") (pintype "passive"))
      (node (ref "U25") (pin "62") (pinfunction "GND_62") (pintype "passive"))
      (node (ref "U25") (pin "63") (pinfunction "GND_63") (pintype "passive"))
      (node (ref "U25") (pin "64") (pinfunction "GND_64") (pintype "passive"))
      (node (ref "U25") (pin "65") (pinfunction "GND_65") (pintype "passive"))
      (node (ref "U27") (pin "3") (pinfunction "GND_3") (pintype "passive"))
      (node (ref "U28") (pin "2") (pintype "passive"))
      (node (ref "U3") (pin "1") (pinfunction "A0_1") (pintype "passive"))
      (node (ref "U3") (pin "2") (pinfunction "A1_2") (pintype "passive"))
      (node (ref "U3") (pin "3") (pinfunction "A2_3") (pintype "passive"))
      (node (ref "U3") (pin "4") (pinfunction "GND_4") (pintype "passive"))
      (node (ref "U3") (pin "7") (pinfunction "WP_7") (pintype "passive"))
      (node (ref "U4") (pin "4") (pinfunction "GND_4") (pintype "power_in"))
      (node (ref "U5") (pin "3") (pinfunction "3_3") (pintype "passive"))
      (node (ref "U6") (pin "3") (pinfunction "3_3") (pintype "passive"))
      (node (ref "U7") (pin "3") (pinfunction "3_3") (pintype "passive"))
      (node (ref "U8") (pin "3") (pinfunction "3_3") (pintype "passive"))
      (node (ref "U9") (pin "3") (pinfunction "3_3") (pintype "passive"))
    )
    (net (code "97") (name "Net-(BAT1-VCC)") (class "Default")
      (node (ref "BAT1") (pin "1") (pinfunction "VCC_1") (pintype "passive"))
      (node (ref "U4") (pin "8") (pinfunction "VCC1_8") (pintype "power_in"))
    )
    (net (code "98") (name "Net-(BEEP1-G)") (class "Default")
      (node (ref "BEEP1") (pin "2") (pinfunction "G_2") (pintype "passive"))
      (node (ref "Q1") (pin "3") (pinfunction "C_3") (pintype "passive"))
    )
    (net (code "99") (name "Net-(BEEP1-P)") (class "Default")
      (node (ref "BEEP1") (pin "1") (pinfunction "P_1") (pintype "passive"))
      (node (ref "R20") (pin "2") (pinfunction "2_2") (pintype "passive"))
    )
    (net (code "100") (name "Net-(C13-VCC)") (class "Default")
      (node (ref "C13") (pin "1") (pinfunction "VCC_1") (pintype "passive"))
      (node (ref "C14") (pin "2") (pintype "passive"))
      (node (ref "D9") (pin "2") (pintype "passive"))
      (node (ref "U13") (pin "1") (pinfunction "+Vin_1") (pintype "passive"))
    )
    (net (code "101") (name "Net-(C35-VCC)") (class "Default")
      (node (ref "C35") (pin "1") (pinfunction "VCC_1") (pintype "passive"))
      (node (ref "U25") (pin "26") (pinfunction "VRTC_26") (pintype "passive"))
    )
    (net (code "102") (name "Net-(C41-Pad1)") (class "Default")
      (node (ref "C41") (pin "1") (pinfunction "1_1") (pintype "passive"))
      (node (ref "RN1") (pin "1") (pinfunction "1_1") (pintype "passive"))
      (node (ref "RN1") (pin "3") (pinfunction "3_3") (pintype "passive"))
    )
    (net (code "103") (name "Net-(C42-Pad1)") (class "Default")
      (node (ref "C42") (pin "1") (pinfunction "1_1") (pintype "passive"))
      (node (ref "L6") (pin "1") (pinfunction "1_1") (pintype "passive"))
      (node (ref "RN1") (pin "5") (pinfunction "5_5") (pintype "passive"))
      (node (ref "RN1") (pin "7") (pinfunction "7_7") (pintype "passive"))
    )
    (net (code "104") (name "Net-(C44-Pad1)") (class "Default")
      (node (ref "C44") (pin "1") (pinfunction "1_1") (pintype "passive"))
      (node (ref "D1") (pin "1") (pintype "passive"))
      (node (ref "R25") (pin "2") (pintype "passive"))
      (node (ref "R33") (pin "2") (pintype "passive"))
    )
    (net (code "105") (name "Net-(C45-Pad1)") (class "Default")
      (node (ref "C45") (pin "1") (pinfunction "1_1") (pintype "passive"))
      (node (ref "D2") (pin "1") (pintype "passive"))
      (node (ref "R26") (pin "2") (pintype "passive"))
      (node (ref "R34") (pin "2") (pintype "passive"))
    )
    (net (code "106") (name "Net-(C46-Pad1)") (class "Default")
      (node (ref "C46") (pin "1") (pinfunction "1_1") (pintype "passive"))
      (node (ref "D3") (pin "1") (pintype "passive"))
      (node (ref "R27") (pin "2") (pintype "passive"))
      (node (ref "R35") (pin "2") (pintype "passive"))
    )
    (net (code "107") (name "Net-(C47-Pad1)") (class "Default")
      (node (ref "C47") (pin "1") (pinfunction "1_1") (pintype "passive"))
      (node (ref "D4") (pin "1") (pintype "passive"))
      (node (ref "R28") (pin "2") (pintype "passive"))
      (node (ref "R36") (pin "2") (pintype "passive"))
    )
    (net (code "108") (name "Net-(C48-Pad1)") (class "Default")
      (node (ref "C48") (pin "1") (pinfunction "1_1") (pintype "passive"))
      (node (ref "D5") (pin "1") (pintype "passive"))
      (node (ref "R29") (pin "2") (pintype "passive"))
      (node (ref "R37") (pin "2") (pintype "passive"))
    )
    (net (code "109") (name "Net-(C49-Pad1)") (class "Default")
      (node (ref "C49") (pin "1") (pinfunction "1_1") (pintype "passive"))
      (node (ref "D6") (pin "1") (pintype "passive"))
      (node (ref "R30") (pin "2") (pintype "passive"))
      (node (ref "R38") (pin "2") (pintype "passive"))
    )
    (net (code "110") (name "Net-(C50-Pad1)") (class "Default")
      (node (ref "C50") (pin "1") (pinfunction "1_1") (pintype "passive"))
      (node (ref "D7") (pin "1") (pintype "passive"))
      (node (ref "R31") (pin "2") (pintype "passive"))
      (node (ref "R39") (pin "2") (pintype "passive"))
    )
    (net (code "111") (name "Net-(C51-Pad1)") (class "Default")
      (node (ref "C51") (pin "1") (pinfunction "1_1") (pintype "passive"))
      (node (ref "D8") (pin "1") (pintype "passive"))
      (node (ref "R32") (pin "2") (pintype "passive"))
      (node (ref "R40") (pin "2") (pintype "passive"))
    )
    (net (code "112") (name "Net-(C52-Pad1)") (class "Default")
      (node (ref "C52") (pin "1") (pinfunction "1_1") (pintype "passive"))
      (node (ref "D13") (pin "1") (pintype "passive"))
      (node (ref "R54") (pin "2") (pintype "passive"))
      (node (ref "R63") (pin "2") (pintype "passive"))
    )
    (net (code "113") (name "Net-(C53-Pad1)") (class "Default")
      (node (ref "C53") (pin "1") (pinfunction "1_1") (pintype "passive"))
      (node (ref "D14") (pin "1") (pintype "passive"))
      (node (ref "R55") (pin "2") (pintype "passive"))
      (node (ref "R64") (pin "2") (pintype "passive"))
    )
    (net (code "114") (name "Net-(C54-Pad1)") (class "Default")
      (node (ref "C54") (pin "1") (pinfunction "1_1") (pintype "passive"))
      (node (ref "D15") (pin "1") (pintype "passive"))
      (node (ref "R56") (pin "2") (pintype "passive"))
      (node (ref "R65") (pin "2") (pintype "passive"))
    )
    (net (code "115") (name "Net-(C55-Pad1)") (class "Default")
      (node (ref "C55") (pin "1") (pinfunction "1_1") (pintype "passive"))
      (node (ref "D16") (pin "1") (pintype "passive"))
      (node (ref "R57") (pin "2") (pintype "passive"))
      (node (ref "R66") (pin "2") (pintype "passive"))
    )
    (net (code "116") (name "Net-(C56-Pad1)") (class "Default")
      (node (ref "C56") (pin "1") (pinfunction "1_1") (pintype "passive"))
      (node (ref "D17") (pin "1") (pintype "passive"))
      (node (ref "R58") (pin "2") (pintype "passive"))
      (node (ref "R67") (pin "2") (pintype "passive"))
    )
    (net (code "117") (name "Net-(C57-Pad1)") (class "Default")
      (node (ref "C57") (pin "1") (pinfunction "1_1") (pintype "passive"))
      (node (ref "D18") (pin "1") (pintype "passive"))
      (node (ref "R59") (pin "2") (pintype "passive"))
      (node (ref "R68") (pin "2") (pintype "passive"))
    )
    (net (code "118") (name "Net-(C58-Pad1)") (class "Default")
      (node (ref "C58") (pin "1") (pinfunction "1_1") (pintype "passive"))
      (node (ref "D19") (pin "1") (pintype "passive"))
      (node (ref "R60") (pin "2") (pintype "passive"))
      (node (ref "R69") (pin "2") (pintype "passive"))
    )
    (net (code "119") (name "Net-(C59-Pad1)") (class "Default")
      (node (ref "C59") (pin "1") (pinfunction "1_1") (pintype "passive"))
      (node (ref "D20") (pin "1") (pintype "passive"))
      (node (ref "R61") (pin "2") (pintype "passive"))
      (node (ref "R70") (pin "2") (pintype "passive"))
    )
    (net (code "120") (name "Net-(D1-Pad2)") (class "Default")
      (node (ref "D1") (pin "2") (pintype "passive"))
      (node (ref "U5") (pin "1") (pinfunction "1_1") (pintype "passive"))
    )
    (net (code "121") (name "Net-(D2-Pad2)") (class "Default")
      (node (ref "D2") (pin "2") (pintype "passive"))
      (node (ref "U6") (pin "1") (pinfunction "1_1") (pintype "passive"))
    )
    (net (code "122") (name "Net-(D3-Pad2)") (class "Default")
      (node (ref "D3") (pin "2") (pintype "passive"))
      (node (ref "U7") (pin "1") (pinfunction "1_1") (pintype "passive"))
    )
    (net (code "123") (name "Net-(D4-Pad2)") (class "Default")
      (node (ref "D4") (pin "2") (pintype "passive"))
      (node (ref "U8") (pin "1") (pinfunction "1_1") (pintype "passive"))
    )
    (net (code "124") (name "Net-(D5-Pad2)") (class "Default")
      (node (ref "D5") (pin "2") (pintype "passive"))
      (node (ref "U9") (pin "1") (pinfunction "1_1") (pintype "passive"))
    )
    (net (code "125") (name "Net-(D6-Pad2)") (class "Default")
      (node (ref "D6") (pin "2") (pintype "passive"))
      (node (ref "U10") (pin "1") (pinfunction "1_1") (pintype "passive"))
    )
    (net (code "126") (name "Net-(D7-Pad2)") (class "Default")
      (node (ref "D7") (pin "2") (pintype "passive"))
      (node (ref "U11") (pin "1") (pinfunction "1_1") (pintype "passive"))
    )
    (net (code "127") (name "Net-(D8-Pad2)") (class "Default")
      (node (ref "D8") (pin "2") (pintype "passive"))
      (node (ref "U12") (pin "1") (pinfunction "1_1") (pintype "passive"))
    )
    (net (code "128") (name "Net-(D10-Pad2)") (class "Default")
      (node (ref "D10") (pin "2") (pinfunction "2_2") (pintype "passive"))
      (node (ref "R41") (pin "2") (pinfunction "2_2") (pintype "passive"))
    )
    (net (code "129") (name "Net-(D11-Pad2)") (class "Default")
      (node (ref "D11") (pin "2") (pinfunction "2_2") (pintype "passive"))
      (node (ref "R42") (pin "1") (pinfunction "1_1") (pintype "passive"))
    )
    (net (code "130") (name "Net-(D12-K)") (class "Default")
      (node (ref "D12") (pin "2") (pinfunction "K_2") (pintype "passive"))
      (node (ref "L5") (pin "1") (pinfunction "1_1") (pintype "passive"))
      (node (ref "U13") (pin "2") (pinfunction "OUT_2") (pintype "passive"))
    )
    (net (code "131") (name "Net-(D13-Pad2)") (class "Default")
      (node (ref "D13") (pin "2") (pintype "passive"))
      (node (ref "U15") (pin "1") (pinfunction "1_1") (pintype "passive"))
    )
    (net (code "132") (name "Net-(D14-Pad2)") (class "Default")
      (node (ref "D14") (pin "2") (pintype "passive"))
      (node (ref "U16") (pin "1") (pinfunction "1_1") (pintype "passive"))
    )
    (net (code "133") (name "Net-(D15-Pad2)") (class "Default")
      (node (ref "D15") (pin "2") (pintype "passive"))
      (node (ref "U17") (pin "1") (pinfunction "1_1") (pintype "passive"))
    )
    (net (code "134") (name "Net-(D16-Pad2)") (class "Default")
      (node (ref "D16") (pin "2") (pintype "passive"))
      (node (ref "U18") (pin "1") (pinfunction "1_1") (pintype "passive"))
    )
    (net (code "135") (name "Net-(D17-Pad2)") (class "Default")
      (node (ref "D17") (pin "2") (pintype "passive"))
      (node (ref "U19") (pin "1") (pinfunction "1_1") (pintype "passive"))
    )
    (net (code "136") (name "Net-(D18-Pad2)") (class "Default")
      (node (ref "D18") (pin "2") (pintype "passive"))
      (node (ref "U20") (pin "1") (pinfunction "1_1") (pintype "passive"))
    )
    (net (code "137") (name "Net-(D19-Pad2)") (class "Default")
      (node (ref "D19") (pin "2") (pintype "passive"))
      (node (ref "U21") (pin "1") (pinfunction "1_1") (pintype "passive"))
    )
    (net (code "138") (name "Net-(D20-Pad2)") (class "Default")
      (node (ref "D20") (pin "2") (pintype "passive"))
      (node (ref "U22") (pin "1") (pinfunction "1_1") (pintype "passive"))
    )
    (net (code "139") (name "Net-(D24-K)") (class "Default")
      (node (ref "D24") (pin "2") (pinfunction "K_2") (pintype "passive"))
      (node (ref "Q6") (pin "3") (pinfunction "C_3") (pintype "passive"))
      (node (ref "R89") (pin "1") (pinfunction "1_1") (pintype "passive"))
    )
    (net (code "140") (name "Net-(D25-Pad1)") (class "Default")
      (node (ref "D25") (pin "1") (pintype "passive"))
      (node (ref "R96") (pin "1") (pintype "passive"))
    )
    (net (code "141") (name "Net-(D26-Pad1)") (class "Default")
      (node (ref "D26") (pin "1") (pintype "passive"))
      (node (ref "R88") (pin "1") (pinfunction "1_1") (pintype "passive"))
    )
    (net (code "142") (name "Net-(D27-Pad1)") (class "Default")
      (node (ref "D27") (pin "1") (pintype "passive"))
      (node (ref "R115") (pin "1") (pinfunction "1_1") (pintype "passive"))
    )
    (net (code "143") (name "Net-(J5-D+)") (class "Default")
      (node (ref "J5") (pin "3") (pinfunction "D+_3") (pintype "passive"))
      (node (ref "R113") (pin "2") (pinfunction "2_2") (pintype "passive"))
    )
    (net (code "144") (name "Net-(J5-D-)") (class "Default")
      (node (ref "J5") (pin "2") (pinfunction "D-_2") (pintype "passive"))
      (node (ref "R111") (pin "2") (pinfunction "2_2") (pintype "passive"))
    )
    (net (code "145") (name "Net-(J6-L+)") (class "Default")
      (node (ref "J6") (pin "9") (pinfunction "L+_9") (pintype "passive"))
      (node (ref "R106") (pin "1") (pinfunction "1_1") (pintype "passive"))
    )
    (net (code "146") (name "Net-(J6-R+)") (class "Default")
      (node (ref "J6") (pin "12") (pinfunction "R+_12") (pintype "passive"))
      (node (ref "R107") (pin "1") (pinfunction "1_1") (pintype "passive"))
    )
    (net (code "147") (name "Net-(J6-RD+)") (class "Default")
      (node (ref "J6") (pin "3") (pinfunction "RD+_3") (pintype "passive"))
      (node (ref "RN1") (pin "6") (pinfunction "6_6") (pintype "passive"))
      (node (ref "U24") (pin "17") (pinfunction "TPOUT+_17") (pintype "passive"))
    )
    (net (code "148") (name "Net-(J6-RD-)") (class "Default")
      (node (ref "J6") (pin "6") (pinfunction "RD-_6") (pintype "passive"))
      (node (ref "RN1") (pin "8") (pinfunction "8_8") (pintype "passive"))
      (node (ref "U24") (pin "16") (pinfunction "TPOUT-_16") (pintype "passive"))
    )
    (net (code "149") (name "Net-(J6-TD+)") (class "Default")
      (node (ref "J6") (pin "1") (pinfunction "TD+_1") (pintype "passive"))
      (node (ref "RN1") (pin "2") (pinfunction "2_2") (pintype "passive"))
      (node (ref "U24") (pin "13") (pinfunction "TPIN+_13") (pintype "passive"))
    )
    (net (code "150") (name "Net-(J6-TD-)") (class "Default")
      (node (ref "J6") (pin "2") (pinfunction "TD-_2") (pintype "passive"))
      (node (ref "RN1") (pin "4") (pinfunction "4_4") (pintype "passive"))
      (node (ref "U24") (pin "12") (pinfunction "TPIN-_12") (pintype "passive"))
    )
    (net (code "151") (name "Net-(J7-Pad1)") (class "Default")
      (node (ref "J7") (pin "1") (pinfunction "1_1") (pintype "passive"))
      (node (ref "K5") (pin "1") (pinfunction "1_1") (pintype "passive"))
    )
    (net (code "152") (name "Net-(J7-Pad2)") (class "Default")
      (node (ref "J7") (pin "2") (pinfunction "2_2") (pintype "passive"))
      (node (ref "K5") (pin "2") (pinfunction "2_2") (pintype "passive"))
    )
    (net (code "153") (name "Net-(J7-Pad3)") (class "Default")
      (node (ref "J7") (pin "3") (pinfunction "3_3") (pintype "passive"))
      (node (ref "K6") (pin "1") (pinfunction "1_1") (pintype "passive"))
    )
    (net (code "154") (name "Net-(J7-Pad4)") (class "Default")
      (node (ref "J7") (pin "4") (pinfunction "4_4") (pintype "passive"))
      (node (ref "K6") (pin "2") (pinfunction "2_2") (pintype "passive"))
    )
    (net (code "155") (name "Net-(J7-Pad5)") (class "Default")
      (node (ref "J7") (pin "5") (pinfunction "5_5") (pintype "passive"))
      (node (ref "K7") (pin "1") (pinfunction "1_1") (pintype "passive"))
    )
    (net (code "156") (name "Net-(J7-Pad6)") (class "Default")
      (node (ref "J7") (pin "6") (pinfunction "6_6") (pintype "passive"))
      (node (ref "K7") (pin "2") (pinfunction "2_2") (pintype "passive"))
    )
    (net (code "157") (name "Net-(J7-Pad7)") (class "Default")
      (node (ref "J7") (pin "7") (pinfunction "7_7") (pintype "passive"))
      (node (ref "K8") (pin "1") (pinfunction "1_1") (pintype "passive"))
    )
    (net (code "158") (name "Net-(J7-Pad8)") (class "Default")
      (node (ref "J7") (pin "8") (pinfunction "8_8") (pintype "passive"))
      (node (ref "K8") (pin "2") (pinfunction "2_2") (pintype "passive"))
    )
    (net (code "159") (name "Net-(LED1-Pad1)") (class "Default")
      (node (ref "LED1") (pin "1") (pinfunction "1_1") (pintype "passive"))
      (node (ref "R11") (pin "1") (pintype "passive"))
    )
    (net (code "160") (name "Net-(LED1-Pad3)") (class "Default")
      (node (ref "LED1") (pin "3") (pinfunction "3_3") (pintype "passive"))
      (node (ref "R10") (pin "1") (pintype "passive"))
    )
    (net (code "161") (name "Net-(LED2-Pad1)") (class "Default")
      (node (ref "LED2") (pin "1") (pinfunction "1_1") (pintype "passive"))
      (node (ref "R13") (pin "1") (pintype "passive"))
    )
    (net (code "162") (name "Net-(LED2-Pad3)") (class "Default")
      (node (ref "LED2") (pin "3") (pinfunction "3_3") (pintype "passive"))
      (node (ref "R12") (pin "1") (pintype "passive"))
    )
    (net (code "163") (name "Net-(LED3-Pad1)") (class "Default")
      (node (ref "LED3") (pin "1") (pinfunction "1_1") (pintype "passive"))
      (node (ref "R15") (pin "1") (pintype "passive"))
    )
    (net (code "164") (name "Net-(LED3-Pad3)") (class "Default")
      (node (ref "LED3") (pin "3") (pinfunction "3_3") (pintype "passive"))
      (node (ref "R14") (pin "1") (pintype "passive"))
    )
    (net (code "165") (name "Net-(LED4-Pad1)") (class "Default")
      (node (ref "LED4") (pin "1") (pinfunction "1_1") (pintype "passive"))
      (node (ref "R17") (pin "1") (pintype "passive"))
    )
    (net (code "166") (name "Net-(LED4-Pad3)") (class "Default")
      (node (ref "LED4") (pin "3") (pinfunction "3_3") (pintype "passive"))
      (node (ref "R16") (pin "1") (pintype "passive"))
    )
    (net (code "167") (name "Net-(LED5-Pad1)") (class "Default")
      (node (ref "LED5") (pin "1") (pintype "passive"))
      (node (ref "R62") (pin "2") (pintype "passive"))
    )
    (net (code "168") (name "Net-(P1-Signal)") (class "Default")
      (node (ref "C33") (pin "1") (pintype "passive"))
      (node (ref "P1") (pin "1") (pinfunction "Signal_1") (pintype "input"))
      (node (ref "R103") (pin "1") (pintype "passive"))
    )
    (net (code "169") (name "Net-(Q1-B)") (class "Default")
      (node (ref "Q1") (pin "2") (pinfunction "B_2") (pintype "passive"))
      (node (ref "R19") (pin "2") (pintype "passive"))
      (node (ref "R21") (pin "2") (pintype "passive"))
    )
    (net (code "170") (name "Net-(Q2-G)") (class "Default")
      (node (ref "Q2") (pin "1") (pinfunction "G_1") (pintype "input"))
      (node (ref "R71") (pin "1") (pinfunction "1_1") (pintype "passive"))
      (node (ref "R82") (pin "2") (pinfunction "2_2") (pintype "passive"))
    )
    (net (code "171") (name "Net-(Q3-B)") (class "Default")
      (node (ref "D22") (pin "1") (pintype "passive"))
      (node (ref "Q3") (pin "2") (pinfunction "B_2") (pintype "passive"))
      (node (ref "R83") (pin "2") (pinfunction "2_2") (pintype "passive"))
    )
    (net (code "172") (name "Net-(Q3-C)") (class "Default")
      (node (ref "Q3") (pin "3") (pinfunction "C_3") (pintype "passive"))
      (node (ref "Q4") (pin "1") (pinfunction "G_1") (pintype "input"))
      (node (ref "R84") (pin "1") (pinfunction "1_1") (pintype "passive"))
    )
    (net (code "173") (name "Net-(Q5-B)") (class "Default")
      (node (ref "Q5") (pin "1") (pinfunction "B_1") (pintype "input"))
      (node (ref "R86") (pin "2") (pinfunction "2_2") (pintype "passive"))
    )
    (net (code "174") (name "Net-(Q5-C)") (class "Default")
      (node (ref "Q5") (pin "3") (pinfunction "C_3") (pintype "passive"))
      (node (ref "R85") (pin "2") (pinfunction "2_2") (pintype "passive"))
    )
    (net (code "175") (name "Net-(Q5-E)") (class "Default")
      (node (ref "Q5") (pin "2") (pinfunction "E_2") (pintype "passive"))
      (node (ref "R120") (pin "1") (pinfunction "1_1") (pintype "passive"))
    )
    (net (code "176") (name "Net-(Q6-B)") (class "Default")
      (node (ref "Q6") (pin "1") (pinfunction "B_1") (pintype "input"))
      (node (ref "R95") (pin "1") (pinfunction "1_1") (pintype "passive"))
    )
    (net (code "177") (name "Net-(Q6-E)") (class "Default")
      (node (ref "Q6") (pin "2") (pinfunction "E_2") (pintype "passive"))
      (node (ref "R86") (pin "1") (pinfunction "1_1") (pintype "passive"))
      (node (ref "U23") (pin "14") (pinfunction "DTS#_14") (pintype "passive"))
    )
    (net (code "178") (name "Net-(Q7-B)") (class "Default")
      (node (ref "Q7") (pin "2") (pinfunction "B_2") (pintype "passive"))
      (node (ref "R91") (pin "2") (pintype "passive"))
      (node (ref "R92") (pin "2") (pintype "passive"))
    )
    (net (code "179") (name "Net-(Q8-B)") (class "Default")
      (node (ref "Q8") (pin "2") (pinfunction "B_2") (pintype "passive"))
      (node (ref "R87") (pin "2") (pintype "passive"))
      (node (ref "R93") (pin "2") (pintype "passive"))
    )
    (net (code "180") (name "Net-(Q8-C)") (class "Default")
      (node (ref "C32") (pin "2") (pintype "passive"))
      (node (ref "Q8") (pin "3") (pinfunction "C_3") (pintype "passive"))
      (node (ref "U25") (pin "16") (pinfunction "~{nRESET}_16") (pintype "passive"))
    )
    (net (code "181") (name "Net-(U2-VDDA)") (class "Default")
      (node (ref "C8") (pin "1") (pinfunction "1_1") (pintype "passive"))
      (node (ref "L3") (pin "1") (pinfunction "1_1") (pintype "passive"))
      (node (ref "U2") (pin "22") (pinfunction "VDDA_22") (pintype "power_in"))
    )
    (net (code "182") (name "Net-(U2-VREF+)") (class "Default")
      (node (ref "C5") (pin "2") (pinfunction "2_2") (pintype "passive"))
      (node (ref "L2") (pin "2") (pinfunction "2_2") (pintype "passive"))
      (node (ref "U2") (pin "21") (pinfunction "VREF+_21") (pintype "power_in"))
    )
    (net (code "183") (name "Net-(U2-VREF-)") (class "Default")
      (node (ref "C5") (pin "1") (pinfunction "1_1") (pintype "passive"))
      (node (ref "L1") (pin "2") (pinfunction "2_2") (pintype "passive"))
      (node (ref "U2") (pin "20") (pinfunction "VREF-_20") (pintype "power_in"))
    )
    (net (code "184") (name "Net-(U2-VSSA)") (class "Default")
      (node (ref "C8") (pin "2") (pinfunction "2_2") (pintype "passive"))
      (node (ref "L4") (pin "2") (pinfunction "2_2") (pintype "passive"))
      (node (ref "U2") (pin "19") (pinfunction "VSSA_19") (pintype "power_in"))
    )
    (net (code "185") (name "Net-(U4-X1)") (class "Default")
      (node (ref "C3") (pin "2") (pintype "passive"))
      (node (ref "U4") (pin "2") (pinfunction "X1_2") (pintype "input"))
      (node (ref "Y2") (pin "2") (pinfunction "OSC2_2") (pintype "passive"))
    )
    (net (code "186") (name "Net-(U4-X2)") (class "Default")
      (node (ref "C4") (pin "2") (pintype "passive"))
      (node (ref "U4") (pin "3") (pinfunction "X2_3") (pintype "input"))
      (node (ref "Y2") (pin "1") (pinfunction "OSC1_1") (pintype "passive"))
    )
    (net (code "187") (name "Net-(U14-CE)") (class "Default")
      (node (ref "C15") (pin "1") (pinfunction "1_1") (pintype "passive"))
      (node (ref "D10") (pin "1") (pinfunction "1_1") (pintype "passive"))
      (node (ref "D11") (pin "1") (pinfunction "1_1") (pintype "passive"))
      (node (ref "R51") (pin "2") (pinfunction "2_2") (pintype "passive"))
      (node (ref "U14") (pin "4") (pinfunction "VCC_4") (pintype "passive"))
      (node (ref "U14") (pin "8") (pinfunction "CE_8") (pintype "passive"))
    )
    (net (code "188") (name "Net-(U14-CHRG)") (class "Default")
      (node (ref "R41") (pin "1") (pinfunction "1_1") (pintype "passive"))
      (node (ref "U14") (pin "7") (pinfunction "CHRG_7") (pintype "passive"))
    )
    (net (code "189") (name "Net-(U14-PROG)") (class "Default")
      (node (ref "R52") (pin "1") (pinfunction "1_1") (pintype "passive"))
      (node (ref "R53") (pin "1") (pinfunction "1_1") (pintype "passive"))
      (node (ref "U14") (pin "2") (pinfunction "PROG_2") (pintype "passive"))
    )
    (net (code "190") (name "Net-(U14-STDBY)") (class "Default")
      (node (ref "R42") (pin "2") (pinfunction "2_2") (pintype "passive"))
      (node (ref "U14") (pin "6") (pinfunction "STDBY_6") (pintype "passive"))
    )
    (net (code "191") (name "Net-(U23-DTR#)") (class "Default")
      (node (ref "R95") (pin "2") (pinfunction "2_2") (pintype "passive"))
      (node (ref "U23") (pin "13") (pinfunction "DTR#_13") (pintype "passive"))
    )
    (net (code "192") (name "Net-(U23-V3)") (class "Default")
      (node (ref "C39") (pin "2") (pinfunction "2_2") (pintype "passive"))
      (node (ref "U23") (pin "4") (pinfunction "V3_4") (pintype "passive"))
    )
    (net (code "193") (name "Net-(U23-X0)") (class "Default")
      (node (ref "C34") (pin "2") (pinfunction "2_2") (pintype "passive"))
      (node (ref "U23") (pin "8") (pinfunction "X0_8") (pintype "passive"))
      (node (ref "Y5") (pin "1") (pinfunction "1_1") (pintype "passive"))
    )
    (net (code "194") (name "Net-(U23-X1)") (class "Default")
      (node (ref "C40") (pin "1") (pinfunction "1_1") (pintype "passive"))
      (node (ref "U23") (pin "7") (pinfunction "X1_7") (pintype "passive"))
      (node (ref "Y5") (pin "2") (pinfunction "2_2") (pintype "passive"))
    )
    (net (code "195") (name "Net-(U24-CS)") (class "Default")
      (node (ref "R94") (pin "1") (pinfunction "1_1") (pintype "passive"))
      (node (ref "R97") (pin "1") (pinfunction "1_1") (pintype "passive"))
      (node (ref "U24") (pin "9") (pinfunction "CS_9") (pintype "passive"))
    )
    (net (code "196") (name "Net-(U24-LEDA)") (class "Default")
      (node (ref "R106") (pin "2") (pinfunction "2_2") (pintype "passive"))
      (node (ref "U24") (pin "27") (pinfunction "LEDA_27") (pintype "passive"))
    )
    (net (code "197") (name "Net-(U24-LEDB)") (class "Default")
      (node (ref "R107") (pin "2") (pinfunction "2_2") (pintype "passive"))
      (node (ref "U24") (pin "26") (pinfunction "LEDB_26") (pintype "passive"))
    )
    (net (code "198") (name "Net-(U24-OSC1)") (class "Default")
      (node (ref "C21") (pin "2") (pinfunction "2_2") (pintype "passive"))
      (node (ref "U24") (pin "23") (pinfunction "OSC1_23") (pintype "passive"))
      (node (ref "Y4") (pin "1") (pinfunction "1_1") (pintype "passive"))
    )
    (net (code "199") (name "Net-(U24-OSC2)") (class "Default")
      (node (ref "C20") (pin "2") (pinfunction "2_2") (pintype "passive"))
      (node (ref "U24") (pin "24") (pinfunction "OSC2_24") (pintype "passive"))
      (node (ref "Y4") (pin "2") (pinfunction "2_2") (pintype "passive"))
    )
    (net (code "200") (name "Net-(U24-RBIAS)") (class "Default")
      (node (ref "R90") (pin "1") (pinfunction "1_1") (pintype "passive"))
      (node (ref "U24") (pin "14") (pinfunction "RBIAS_14") (pintype "passive"))
    )
    (net (code "201") (name "Net-(U24-VCAP)") (class "Default")
      (node (ref "C29") (pin "1") (pinfunction "1_1") (pintype "passive"))
      (node (ref "U24") (pin "1") (pinfunction "VCAP_1") (pintype "passive"))
    )
    (net (code "202") (name "Net-(U25-RF)") (class "Default")
      (node (ref "C36") (pin "1") (pintype "passive"))
      (node (ref "R103") (pin "2") (pintype "passive"))
      (node (ref "U25") (pin "60") (pinfunction "RF_60") (pintype "passive"))
    )
    (net (code "203") (name "Net-(U25-RI)") (class "Default")
      (node (ref "R96") (pin "2") (pintype "passive"))
      (node (ref "U25") (pin "4") (pinfunction "RI_4") (pintype "passive"))
    )
    (net (code "204") (name "Net-(U25-STATUS)") (class "Default")
      (node (ref "R88") (pin "2") (pinfunction "2_2") (pintype "passive"))
      (node (ref "U25") (pin "66") (pinfunction "STATUS_66") (pintype "passive"))
    )
    (net (code "205") (name "Net-(U25-netLED)") (class "Default")
      (node (ref "R115") (pin "2") (pinfunction "2_2") (pintype "passive"))
      (node (ref "U25") (pin "52") (pinfunction "netLED_52") (pintype "passive"))
    )
    (net (code "206") (name "Net-(U27-CLK)") (class "Default")
      (node (ref "R116") (pin "1") (pinfunction "1_1") (pintype "passive"))
      (node (ref "U27") (pin "4") (pinfunction "CLK_4") (pintype "passive"))
      (node (ref "U28") (pin "6") (pintype "passive"))
    )
    (net (code "207") (name "Net-(U27-I{slash}O)") (class "Default")
      (node (ref "R118") (pin "1") (pinfunction "1_1") (pintype "passive"))
      (node (ref "U27") (pin "1") (pinfunction "I/O_1") (pintype "passive"))
      (node (ref "U28") (pin "1") (pintype "passive"))
    )
    (net (code "208") (name "Net-(U27-RST)") (class "Default")
      (node (ref "R117") (pin "1") (pinfunction "1_1") (pintype "passive"))
      (node (ref "U27") (pin "5") (pinfunction "RST_5") (pintype "passive"))
      (node (ref "U28") (pin "5") (pintype "passive"))
    )
    (net (code "209") (name "PGND") (class "Default")
      (node (ref "C44") (pin "2") (pinfunction "2_2") (pintype "passive"))
      (node (ref "C45") (pin "2") (pinfunction "2_2") (pintype "passive"))
      (node (ref "C46") (pin "2") (pinfunction "2_2") (pintype "passive"))
      (node (ref "C47") (pin "2") (pinfunction "2_2") (pintype "passive"))
      (node (ref "C48") (pin "2") (pinfunction "2_2") (pintype "passive"))
      (node (ref "C49") (pin "2") (pinfunction "2_2") (pintype "passive"))
      (node (ref "C50") (pin "2") (pinfunction "2_2") (pintype "passive"))
      (node (ref "C51") (pin "2") (pinfunction "2_2") (pintype "passive"))
      (node (ref "C52") (pin "2") (pinfunction "2_2") (pintype "passive"))
      (node (ref "C53") (pin "2") (pinfunction "2_2") (pintype "passive"))
      (node (ref "C54") (pin "2") (pinfunction "2_2") (pintype "passive"))
      (node (ref "C55") (pin "2") (pinfunction "2_2") (pintype "passive"))
      (node (ref "C56") (pin "2") (pinfunction "2_2") (pintype "passive"))
      (node (ref "C57") (pin "2") (pinfunction "2_2") (pintype "passive"))
      (node (ref "C58") (pin "2") (pinfunction "2_2") (pintype "passive"))
      (node (ref "C59") (pin "2") (pinfunction "2_2") (pintype "passive"))
      (node (ref "J10") (pin "1") (pinfunction "1_1") (pintype "passive"))
      (node (ref "J10") (pin "2") (pinfunction "2_2") (pintype "passive"))
      (node (ref "J10") (pin "3") (pinfunction "3_3") (pintype "passive"))
      (node (ref "J10") (pin "4") (pinfunction "4_4") (pintype "passive"))
      (node (ref "R33") (pin "1") (pintype "passive"))
      (node (ref "R34") (pin "1") (pintype "passive"))
      (node (ref "R35") (pin "1") (pintype "passive"))
      (node (ref "R36") (pin "1") (pintype "passive"))
      (node (ref "R37") (pin "1") (pintype "passive"))
      (node (ref "R38") (pin "1") (pintype "passive"))
      (node (ref "R39") (pin "1") (pintype "passive"))
      (node (ref "R40") (pin "1") (pintype "passive"))
      (node (ref "R63") (pin "1") (pintype "passive"))
      (node (ref "R64") (pin "1") (pintype "passive"))
      (node (ref "R65") (pin "1") (pintype "passive"))
      (node (ref "R66") (pin "1") (pintype "passive"))
      (node (ref "R67") (pin "1") (pintype "passive"))
      (node (ref "R68") (pin "1") (pintype "passive"))
      (node (ref "R69") (pin "1") (pintype "passive"))
      (node (ref "R70") (pin "1") (pintype "passive"))
      (node (ref "U10") (pin "2") (pinfunction "2_2") (pintype "passive"))
      (node (ref "U11") (pin "2") (pinfunction "2_2") (pintype "passive"))
      (node (ref "U12") (pin "2") (pinfunction "2_2") (pintype "passive"))
      (node (ref "U15") (pin "2") (pinfunction "2_2") (pintype "passive"))
      (node (ref "U16") (pin "2") (pinfunction "2_2") (pintype "passive"))
      (node (ref "U17") (pin "2") (pinfunction "2_2") (pintype "passive"))
      (node (ref "U18") (pin "2") (pinfunction "2_2") (pintype "passive"))
      (node (ref "U19") (pin "2") (pinfunction "2_2") (pintype "passive"))
      (node (ref "U20") (pin "2") (pinfunction "2_2") (pintype "passive"))
      (node (ref "U21") (pin "2") (pinfunction "2_2") (pintype "passive"))
      (node (ref "U22") (pin "2") (pinfunction "2_2") (pintype "passive"))
      (node (ref "U5") (pin "2") (pinfunction "2_2") (pintype "passive"))
      (node (ref "U6") (pin "2") (pinfunction "2_2") (pintype "passive"))
      (node (ref "U7") (pin "2") (pinfunction "2_2") (pintype "passive"))
      (node (ref "U8") (pin "2") (pinfunction "2_2") (pintype "passive"))
      (node (ref "U9") (pin "2") (pinfunction "2_2") (pintype "passive"))
    )
    (net (code "210") (name "V1") (class "Default")
      (node (ref "C37") (pin "1") (pinfunction "VCC_1") (pintype "passive"))
      (node (ref "C38") (pin "1") (pintype "passive"))
      (node (ref "D23") (pin "1") (pinfunction "A_1") (pintype "passive"))
      (node (ref "Q4") (pin "2") (pinfunction "D_2") (pintype "input"))
      (node (ref "U25") (pin "55") (pinfunction "VBAT_55") (pintype "passive"))
      (node (ref "U25") (pin "56") (pinfunction "VBAT_56") (pintype "passive"))
      (node (ref "U25") (pin "57") (pinfunction "VBAT_57") (pintype "passive"))
    )
    (net (code "211") (name "VBAT") (class "Default")
      (node (ref "C16") (pin "1") (pinfunction "1_1") (pintype "passive"))
      (node (ref "J4") (pin "1") (pinfunction "1_1") (pintype "passive"))
      (node (ref "Q2") (pin "2") (pinfunction "D_2") (pintype "input"))
      (node (ref "U14") (pin "5") (pinfunction "BAT_5") (pintype "passive"))
    )
    (net (code "212") (name "VCC+3.3V") (class "Default")
      (node (ref "C10") (pin "1") (pintype "passive"))
      (node (ref "C19") (pin "1") (pinfunction "1_1") (pintype "passive"))
      (node (ref "C22") (pin "1") (pinfunction "1_1") (pintype "passive"))
      (node (ref "C23") (pin "2") (pinfunction "2_2") (pintype "passive"))
      (node (ref "C24") (pin "1") (pinfunction "1_1") (pintype "passive"))
      (node (ref "C25") (pin "1") (pinfunction "1_1") (pintype "passive"))
      (node (ref "C26") (pin "1") (pinfunction "1_1") (pintype "passive"))
      (node (ref "C27") (pin "1") (pinfunction "1_1") (pintype "passive"))
      (node (ref "C28") (pin "1") (pinfunction "1_1") (pintype "passive"))
      (node (ref "C43") (pin "1") (pinfunction "1_1") (pintype "passive"))
      (node (ref "C69") (pin "2") (pinfunction "2_2") (pintype "passive"))
      (node (ref "C70") (pin "2") (pinfunction "2_2") (pintype "passive"))
      (node (ref "C71") (pin "2") (pinfunction "2_2") (pintype "passive"))
      (node (ref "C72") (pin "2") (pinfunction "2_2") (pintype "passive"))
      (node (ref "C73") (pin "2") (pinfunction "2_2") (pintype "passive"))
      (node (ref "C9") (pin "1") (pintype "passive"))
      (node (ref "D23") (pin "2") (pinfunction "K_2") (pintype "passive"))
      (node (ref "J6") (pin "4") (pinfunction "4_4") (pintype "passive"))
      (node (ref "J6") (pin "5") (pinfunction "5_5") (pintype "passive"))
      (node (ref "JTAG_1") (pin "1") (pinfunction "VTref_1") (pintype "passive"))
      (node (ref "JTAG_1") (pin "2") (pinfunction "VTref_2") (pintype "passive"))
      (node (ref "L2") (pin "1") (pinfunction "1_1") (pintype "passive"))
      (node (ref "L3") (pin "2") (pinfunction "2_2") (pintype "passive"))
      (node (ref "L6") (pin "2") (pinfunction "2_2") (pintype "passive"))
      (node (ref "LED1") (pin "2") (pinfunction "2_2") (pintype "passive"))
      (node (ref "LED2") (pin "2") (pinfunction "2_2") (pintype "passive"))
      (node (ref "LED3") (pin "2") (pinfunction "2_2") (pintype "passive"))
      (node (ref "LED4") (pin "2") (pinfunction "2_2") (pintype "passive"))
      (node (ref "R101") (pin "1") (pintype "passive"))
      (node (ref "R102") (pin "1") (pintype "passive"))
      (node (ref "R104") (pin "1") (pintype "passive"))
      (node (ref "R18") (pin "2") (pintype "passive"))
      (node (ref "R22") (pin "1") (pintype "passive"))
      (node (ref "R23") (pin "2") (pintype "passive"))
      (node (ref "R24") (pin "2") (pintype "passive"))
      (node (ref "R3") (pin "1") (pintype "passive"))
      (node (ref "R4") (pin "1") (pintype "passive"))
      (node (ref "R43") (pin "2") (pintype "passive"))
      (node (ref "R44") (pin "2") (pintype "passive"))
      (node (ref "R45") (pin "2") (pintype "passive"))
      (node (ref "R46") (pin "2") (pintype "passive"))
      (node (ref "R47") (pin "2") (pintype "passive"))
      (node (ref "R48") (pin "2") (pintype "passive"))
      (node (ref "R49") (pin "2") (pintype "passive"))
      (node (ref "R5") (pin "1") (pintype "passive"))
      (node (ref "R50") (pin "2") (pintype "passive"))
      (node (ref "R74") (pin "2") (pintype "passive"))
      (node (ref "R75") (pin "2") (pintype "passive"))
      (node (ref "R76") (pin "2") (pintype "passive"))
      (node (ref "R77") (pin "2") (pintype "passive"))
      (node (ref "R78") (pin "2") (pintype "passive"))
      (node (ref "R79") (pin "2") (pintype "passive"))
      (node (ref "R80") (pin "2") (pintype "passive"))
      (node (ref "R81") (pin "2") (pintype "passive"))
      (node (ref "R97") (pin "2") (pinfunction "2_2") (pintype "passive"))
      (node (ref "R99") (pin "1") (pintype "passive"))
      (node (ref "U2") (pin "100") (pinfunction "VDD_3_100") (pintype "power_in"))
      (node (ref "U2") (pin "11") (pinfunction "VDD_5_11") (pintype "power_in"))
      (node (ref "U2") (pin "28") (pinfunction "VDD_4_28") (pintype "power_in"))
      (node (ref "U2") (pin "50") (pinfunction "VDD_1_50") (pintype "power_in"))
      (node (ref "U2") (pin "75") (pinfunction "VDD_2_75") (pintype "power_in"))
      (node (ref "U24") (pin "15") (pinfunction "VDDTX_15") (pintype "passive"))
      (node (ref "U24") (pin "19") (pinfunction "VDDRX_19") (pintype "passive"))
      (node (ref "U24") (pin "20") (pinfunction "VDDPLL_20") (pintype "passive"))
      (node (ref "U24") (pin "25") (pinfunction "VDDOSC_25") (pintype "passive"))
      (node (ref "U24") (pin "28") (pinfunction "VDD_28") (pintype "passive"))
      (node (ref "U3") (pin "8") (pinfunction "VCC1_8") (pintype "passive"))
      (node (ref "U4") (pin "1") (pinfunction "VCC2_1") (pintype "power_in"))
    )
    (net (code "213") (name "VCC+5V") (class "Default")
      (node (ref "C17") (pin "1") (pinfunction "VCC_1") (pintype "passive"))
      (node (ref "C18") (pin "2") (pintype "passive"))
      (node (ref "C30") (pin "2") (pinfunction "2_2") (pintype "passive"))
      (node (ref "C31") (pin "2") (pinfunction "2_2") (pintype "passive"))
      (node (ref "D21") (pin "1") (pinfunction "A_1") (pintype "passive"))
      (node (ref "D28") (pin "2") (pintype "passive"))
      (node (ref "D29") (pin "2") (pintype "passive"))
      (node (ref "D30") (pin "2") (pintype "passive"))
      (node (ref "D31") (pin "2") (pintype "passive"))
      (node (ref "J5") (pin "1") (pinfunction "VCC_1") (pintype "passive"))
      (node (ref "K5") (pin "4") (pinfunction "4_4") (pintype "passive"))
      (node (ref "K6") (pin "4") (pinfunction "4_4") (pintype "passive"))
      (node (ref "K7") (pin "4") (pinfunction "4_4") (pintype "passive"))
      (node (ref "K8") (pin "4") (pinfunction "4_4") (pintype "passive"))
      (node (ref "L5") (pin "2") (pinfunction "2_2") (pintype "passive"))
      (node (ref "R120") (pin "2") (pinfunction "2_2") (pintype "passive"))
      (node (ref "R20") (pin "1") (pinfunction "1_1") (pintype "passive"))
      (node (ref "R51") (pin "1") (pinfunction "1_1") (pintype "passive"))
      (node (ref "R62") (pin "1") (pintype "passive"))
      (node (ref "R7") (pin "2") (pintype "passive"))
      (node (ref "R71") (pin "2") (pinfunction "2_2") (pintype "passive"))
      (node (ref "R89") (pin "2") (pinfunction "2_2") (pintype "passive"))
      (node (ref "U13") (pin "4") (pinfunction "FEEDBACK_4") (pintype "passive"))
      (node (ref "U23") (pin "16") (pinfunction "VCC_16") (pintype "passive"))
    )
    (net (code "214") (name "VCC+12V") (class "Default")
      (node (ref "D9") (pin "1") (pintype "passive"))
      (node (ref "J1") (pin "1") (pintype "passive"))
    )
    (net (code "215") (name "Vbt") (class "Default")
      (node (ref "D21") (pin "2") (pinfunction "K_2") (pintype "passive"))
      (node (ref "D22") (pin "2") (pintype "passive"))
      (node (ref "Q2") (pin "3") (pinfunction "S_3") (pintype "input"))
      (node (ref "Q4") (pin "3") (pinfunction "S_3") (pintype "input"))
      (node (ref "R72") (pin "2") (pintype "passive"))
      (node (ref "R84") (pin "2") (pinfunction "2_2") (pintype "passive"))
    )
    (net (code "216") (name "unconnected-(J5-ID-Pad4)") (class "Default")
      (node (ref "J5") (pin "4") (pinfunction "ID_4") (pintype "passive+no_connect"))
    )
    (net (code "217") (name "unconnected-(J6-Pad7)") (class "Default")
      (node (ref "J6") (pin "7") (pinfunction "7_7") (pintype "passive"))
    )
    (net (code "218") (name "unconnected-(JTAG_1-Pad8)") (class "Default")
      (node (ref "JTAG_1") (pin "8") (pinfunction "8_8") (pintype "passive"))
    )
    (net (code "219") (name "unconnected-(P1-GND-Pad3)") (class "Default")
      (node (ref "P1") (pin "3") (pinfunction "GND_3") (pintype "power_in"))
    )
    (net (code "220") (name "unconnected-(P1-GND-Pad4)") (class "Default")
      (node (ref "P1") (pin "4") (pinfunction "GND_4") (pintype "power_in"))
    )
    (net (code "221") (name "unconnected-(P1-GND-Pad5)") (class "Default")
      (node (ref "P1") (pin "5") (pinfunction "GND_5") (pintype "power_in"))
    )
    (net (code "222") (name "unconnected-(U2-NC-Pad73)") (class "Default")
      (node (ref "U2") (pin "73") (pinfunction "NC_73") (pintype "passive+no_connect"))
    )
    (net (code "223") (name "unconnected-(U2-PA12{slash}USART1_RTS{slash}USBDP{slash}CAN_TX{slash}TIM1_ETR-Pad71)") (class "Default")
      (node (ref "U2") (pin "71") (pinfunction "PA12/USART1_RTS/USBDP/CAN_TX/TIM1_ETR_71") (pintype "bidirectional"))
    )
    (net (code "224") (name "unconnected-(U2-PB0{slash}ADC8{slash}TIM3_CH3{slash}TIM1_CH2N-Pad35)") (class "Default")
      (node (ref "U2") (pin "35") (pinfunction "PB0/ADC8/TIM3_CH3/TIM1_CH2N_35") (pintype "bidirectional+no_connect"))
    )
    (net (code "225") (name "unconnected-(U2-PB1{slash}ADC9{slash}TIM3_CH4{slash}TIM1_CH3N-Pad36)") (class "Default")
      (node (ref "U2") (pin "36") (pinfunction "PB1/ADC9/TIM3_CH4/TIM1_CH3N_36") (pintype "bidirectional+no_connect"))
    )
    (net (code "226") (name "unconnected-(U2-PB12{slash}SPI2_NSS{slash}I2C2_SMBAI{slash}USART3_CK{slash}TIM1_BKIN-Pad51)") (class "Default")
      (node (ref "U2") (pin "51") (pinfunction "PB12/SPI2_NSS/I2C2_SMBAI/USART3_CK/TIM1_BKIN_51") (pintype "bidirectional+no_connect"))
    )
    (net (code "227") (name "unconnected-(U2-PB13{slash}SPI2_SCK{slash}USART3_CTS{slash}TIM1CH1N-Pad52)") (class "Default")
      (node (ref "U2") (pin "52") (pinfunction "PB13/SPI2_SCK/USART3_CTS/TIM1CH1N_52") (pintype "bidirectional+no_connect"))
    )
    (net (code "228") (name "unconnected-(U2-PB14{slash}SPI2_MISO{slash}USART3_RTS{slash}TIM1_CH2N-Pad53)") (class "Default")
      (node (ref "U2") (pin "53") (pinfunction "PB14/SPI2_MISO/USART3_RTS/TIM1_CH2N_53") (pintype "bidirectional+no_connect"))
    )
    (net (code "229") (name "unconnected-(U2-PB15{slash}SPI2_MOSI{slash}TIM1_CH3N-Pad54)") (class "Default")
      (node (ref "U2") (pin "54") (pinfunction "PB15/SPI2_MOSI/TIM1_CH3N_54") (pintype "bidirectional+no_connect"))
    )
    (net (code "230") (name "unconnected-(U2-PC3{slash}ADC13-Pad18)") (class "Default")
      (node (ref "U2") (pin "18") (pinfunction "PC3/ADC13_18") (pintype "bidirectional"))
    )
    (net (code "231") (name "unconnected-(U2-PC4{slash}ADC14-Pad33)") (class "Default")
      (node (ref "U2") (pin "33") (pinfunction "PC4/ADC14_33") (pintype "bidirectional"))
    )
    (net (code "232") (name "unconnected-(U2-PC5{slash}ADC15-Pad34)") (class "Default")
      (node (ref "U2") (pin "34") (pinfunction "PC5/ADC15_34") (pintype "bidirectional"))
    )
    (net (code "233") (name "unconnected-(U2-PC13-TAMPER-RTC-Pad7)") (class "Default")
      (node (ref "U2") (pin "7") (pinfunction "PC13-TAMPER-RTC_7") (pintype "bidirectional+no_connect"))
    )
    (net (code "234") (name "unconnected-(U2-PD8{slash}USART3_TX-Pad55)") (class "Default")
      (node (ref "U2") (pin "55") (pinfunction "PD8/USART3_TX_55") (pintype "bidirectional+no_connect"))
    )
    (net (code "235") (name "unconnected-(U2-PD9{slash}USART3_RX-Pad56)") (class "Default")
      (node (ref "U2") (pin "56") (pinfunction "PD9/USART3_RX_56") (pintype "bidirectional"))
    )
    (net (code "236") (name "unconnected-(U2-PD13{slash}TIM4_CH2-Pad60)") (class "Default")
      (node (ref "U2") (pin "60") (pinfunction "PD13/TIM4_CH2_60") (pintype "bidirectional+no_connect"))
    )
    (net (code "237") (name "unconnected-(U2-PD14{slash}TIM4_CH3-Pad61)") (class "Default")
      (node (ref "U2") (pin "61") (pinfunction "PD14/TIM4_CH3_61") (pintype "bidirectional+no_connect"))
    )
    (net (code "238") (name "unconnected-(U2-PD15{slash}TIM4_CH4-Pad62)") (class "Default")
      (node (ref "U2") (pin "62") (pinfunction "PD15/TIM4_CH4_62") (pintype "bidirectional+no_connect"))
    )
    (net (code "239") (name "unconnected-(U2-PE6-Pad5)") (class "Default")
      (node (ref "U2") (pin "5") (pinfunction "PE6_5") (pintype "bidirectional+no_connect"))
    )
    (net (code "240") (name "unconnected-(U2-VBAT-Pad6)") (class "Default")
      (node (ref "U2") (pin "6") (pinfunction "VBAT_6") (pintype "power_in+no_connect"))
    )
    (net (code "241") (name "unconnected-(U23-CTS#-Pad9)") (class "Default")
      (node (ref "U23") (pin "9") (pinfunction "CTS#_9") (pintype "passive+no_connect"))
    )
    (net (code "242") (name "unconnected-(U23-DCD#-Pad12)") (class "Default")
      (node (ref "U23") (pin "12") (pinfunction "DCD#_12") (pintype "passive+no_connect"))
    )
    (net (code "243") (name "unconnected-(U23-DSR#-Pad10)") (class "Default")
      (node (ref "U23") (pin "10") (pinfunction "DSR#_10") (pintype "passive+no_connect"))
    )
    (net (code "244") (name "unconnected-(U23-R1#-Pad11)") (class "Default")
      (node (ref "U23") (pin "11") (pinfunction "R1#_11") (pintype "passive+no_connect"))
    )
    (net (code "245") (name "unconnected-(U23-R232-Pad15)") (class "Default")
      (node (ref "U23") (pin "15") (pinfunction "R232_15") (pintype "passive+no_connect"))
    )
    (net (code "246") (name "unconnected-(U24-CLKOUT-Pad3)") (class "Default")
      (node (ref "U24") (pin "3") (pinfunction "CLKOUT_3") (pintype "passive+no_connect"))
    )
    (net (code "247") (name "unconnected-(U25-ADC-Pad25)") (class "Default")
      (node (ref "U25") (pin "25") (pinfunction "ADC_25") (pintype "passive+no_connect"))
    )
    (net (code "248") (name "unconnected-(U25-CTS-Pad7)") (class "Default")
      (node (ref "U25") (pin "7") (pinfunction "CTS_7") (pintype "passive+no_connect"))
    )
    (net (code "249") (name "unconnected-(U25-DBG_RXD-Pad28)") (class "Default")
      (node (ref "U25") (pin "28") (pinfunction "DBG_RXD_28") (pintype "passive+no_connect"))
    )
    (net (code "250") (name "unconnected-(U25-DBG_TXD-Pad27)") (class "Default")
      (node (ref "U25") (pin "27") (pinfunction "DBG_TXD_27") (pintype "passive+no_connect"))
    )
    (net (code "251") (name "unconnected-(U25-DCD-Pad5)") (class "Default")
      (node (ref "U25") (pin "5") (pinfunction "DCD_5") (pintype "passive+no_connect"))
    )
    (net (code "252") (name "unconnected-(U25-DISP_CLK-Pad11)") (class "Default")
      (node (ref "U25") (pin "11") (pinfunction "DISP_CLK_11") (pintype "passive+no_connect"))
    )
    (net (code "253") (name "unconnected-(U25-DISP_CS-Pad14)") (class "Default")
      (node (ref "U25") (pin "14") (pinfunction "DISP_CS_14") (pintype "passive+no_connect"))
    )
    (net (code "254") (name "unconnected-(U25-DISP_DATA-Pad12)") (class "Default")
      (node (ref "U25") (pin "12") (pinfunction "DISP_DATA_12") (pintype "passive+no_connect"))
    )
    (net (code "255") (name "unconnected-(U25-DISP_D{slash}C-Pad13)") (class "Default")
      (node (ref "U25") (pin "13") (pinfunction "DISP_D/C_13") (pintype "passive+no_connect"))
    )
    (net (code "256") (name "unconnected-(U25-DSR-Pad6)") (class "Default")
      (node (ref "U25") (pin "6") (pinfunction "DSR_6") (pintype "passive+no_connect"))
    )
    (net (code "257") (name "unconnected-(U25-DTR-Pad3)") (class "Default")
      (node (ref "U25") (pin "3") (pinfunction "DTR_3") (pintype "passive+no_connect"))
    )
    (net (code "258") (name "unconnected-(U25-GND-Pad17)") (class "Default")
      (node (ref "U25") (pin "17") (pinfunction "GND_17") (pintype "passive"))
    )
    (net (code "259") (name "unconnected-(U25-GPIO1{slash}KBR4-Pad40)") (class "Default")
      (node (ref "U25") (pin "40") (pinfunction "GPIO1/KBR4_40") (pintype "passive+no_connect"))
    )
    (net (code "260") (name "unconnected-(U25-GPIO2{slash}KBR3-Pad41)") (class "Default")
      (node (ref "U25") (pin "41") (pinfunction "GPIO2/KBR3_41") (pintype "passive+no_connect"))
    )
    (net (code "261") (name "unconnected-(U25-GPIO3{slash}KBR2-Pad42)") (class "Default")
      (node (ref "U25") (pin "42") (pinfunction "GPIO3/KBR2_42") (pintype "passive+no_connect"))
    )
    (net (code "262") (name "unconnected-(U25-GPIO4{slash}KBR1-Pad43)") (class "Default")
      (node (ref "U25") (pin "43") (pinfunction "GPIO4/KBR1_43") (pintype "passive+no_connect"))
    )
    (net (code "263") (name "unconnected-(U25-GPIO5{slash}KBR0-Pad44)") (class "Default")
      (node (ref "U25") (pin "44") (pinfunction "GPIO5/KBR0_44") (pintype "passive+no_connect"))
    )
    (net (code "264") (name "unconnected-(U25-GPIO6{slash}KBC4-Pad47)") (class "Default")
      (node (ref "U25") (pin "47") (pinfunction "GPIO6/KBC4_47") (pintype "passive+no_connect"))
    )
    (net (code "265") (name "unconnected-(U25-GPIO7{slash}KBC3-Pad48)") (class "Default")
      (node (ref "U25") (pin "48") (pinfunction "GPIO7/KBC3_48") (pintype "passive+no_connect"))
    )
    (net (code "266") (name "unconnected-(U25-GPIO8{slash}KBC2-Pad49)") (class "Default")
      (node (ref "U25") (pin "49") (pinfunction "GPIO8/KBC2_49") (pintype "passive+no_connect"))
    )
    (net (code "267") (name "unconnected-(U25-GPIO9{slash}KBC1-Pad50)") (class "Default")
      (node (ref "U25") (pin "50") (pinfunction "GPIO9/KBC1_50") (pintype "passive+no_connect"))
    )
    (net (code "268") (name "unconnected-(U25-GPIO10{slash}KBC0-Pad51)") (class "Default")
      (node (ref "U25") (pin "51") (pinfunction "GPIO10/KBC0_51") (pintype "passive+no_connect"))
    )
    (net (code "269") (name "unconnected-(U25-GPIO11-Pad67)") (class "Default")
      (node (ref "U25") (pin "67") (pinfunction "GPIO11_67") (pintype "passive+no_connect"))
    )
    (net (code "270") (name "unconnected-(U25-GPIO12-Pad68)") (class "Default")
      (node (ref "U25") (pin "68") (pinfunction "GPIO12_68") (pintype "passive+no_connect"))
    )
    (net (code "271") (name "unconnected-(U25-LINE_L-Pad24)") (class "Default")
      (node (ref "U25") (pin "24") (pinfunction "LINE_L_24") (pintype "passive+no_connect"))
    )
    (net (code "272") (name "unconnected-(U25-LINE_R-Pad23)") (class "Default")
      (node (ref "U25") (pin "23") (pinfunction "LINE_R_23") (pintype "passive+no_connect"))
    )
    (net (code "273") (name "unconnected-(U25-MICN-Pad20)") (class "Default")
      (node (ref "U25") (pin "20") (pinfunction "MICN_20") (pintype "passive+no_connect"))
    )
    (net (code "274") (name "unconnected-(U25-MICP-Pad19)") (class "Default")
      (node (ref "U25") (pin "19") (pinfunction "MICP_19") (pintype "passive+no_connect"))
    )
    (net (code "275") (name "unconnected-(U25-PWM1-Pad35)") (class "Default")
      (node (ref "U25") (pin "35") (pinfunction "PWM1_35") (pintype "passive+no_connect"))
    )
    (net (code "276") (name "unconnected-(U25-PWM2-Pad36)") (class "Default")
      (node (ref "U25") (pin "36") (pinfunction "PWM2_36") (pintype "passive+no_connect"))
    )
    (net (code "277") (name "unconnected-(U25-PWRKEYOUT-Pad2)") (class "Default")
      (node (ref "U25") (pin "2") (pinfunction "PWRKEYOUT_2") (pintype "passive+no_connect"))
    )
    (net (code "278") (name "unconnected-(U25-RTS-Pad8)") (class "Default")
      (node (ref "U25") (pin "8") (pinfunction "RTS_8") (pintype "passive+no_connect"))
    )
    (net (code "279") (name "unconnected-(U25-SCL-Pad38)") (class "Default")
      (node (ref "U25") (pin "38") (pinfunction "SCL_38") (pintype "passive+no_connect"))
    )
    (net (code "280") (name "unconnected-(U25-SDA-Pad37)") (class "Default")
      (node (ref "U25") (pin "37") (pinfunction "SDA_37") (pintype "passive+no_connect"))
    )
    (net (code "281") (name "unconnected-(U25-SIM_PRES-Pad34)") (class "Default")
      (node (ref "U25") (pin "34") (pinfunction "SIM_PRES_34") (pintype "passive+no_connect"))
    )
    (net (code "282") (name "unconnected-(U25-SPN-Pad22)") (class "Default")
      (node (ref "U25") (pin "22") (pinfunction "SPN_22") (pintype "passive+no_connect"))
    )
    (net (code "283") (name "unconnected-(U25-SPP-Pad21)") (class "Default")
      (node (ref "U25") (pin "21") (pinfunction "SPP_21") (pintype "passive+no_connect"))
    )
    (net (code "284") (name "unconnected-(U25-VDD_EXT-Pad15)") (class "Default")
      (node (ref "U25") (pin "15") (pinfunction "VDD_EXT_15") (pintype "passive+no_connect"))
    )
    (net (code "285") (name "unconnected-(U27-VPP-Pad2)") (class "Default")
      (node (ref "U27") (pin "2") (pinfunction "VPP_2") (pintype "passive+no_connect"))
    )
    (net (code "286") (name "unconnected-(U28-Pad3)") (class "Default")
      (node (ref "U28") (pin "3") (pintype "passive+no_connect"))
    )
  )
)
